# FOC_DRIVER.net
KiCad netlist of a schematic drawn in Altium Designer
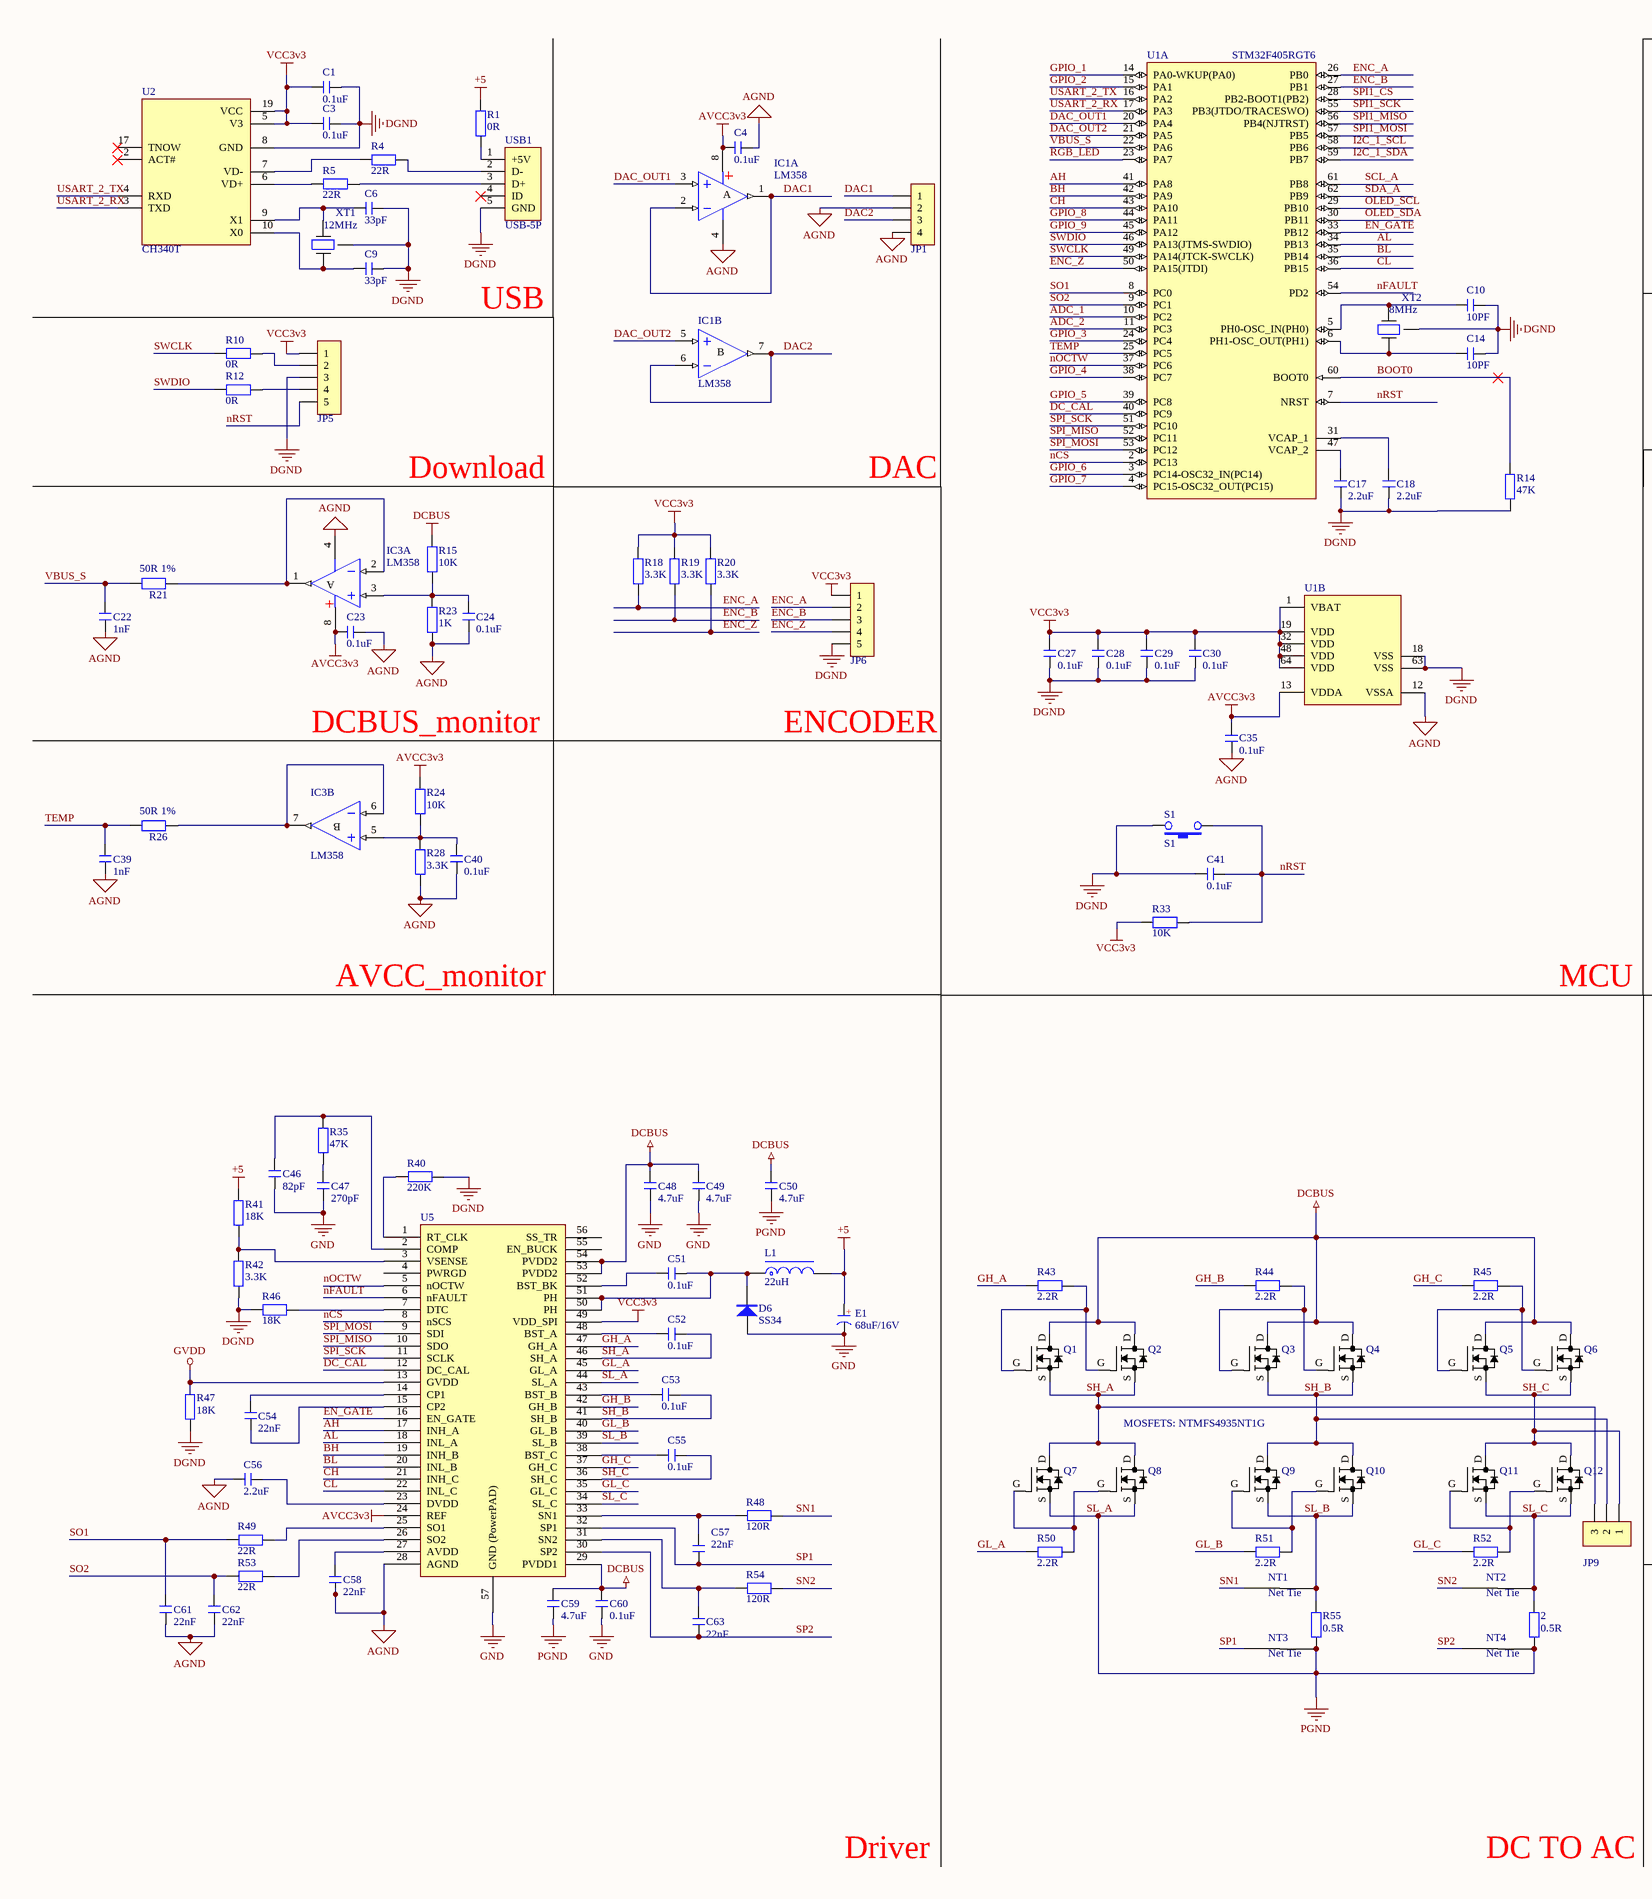
[diagram p0: FOC_DRIVER.SchDoc, left]
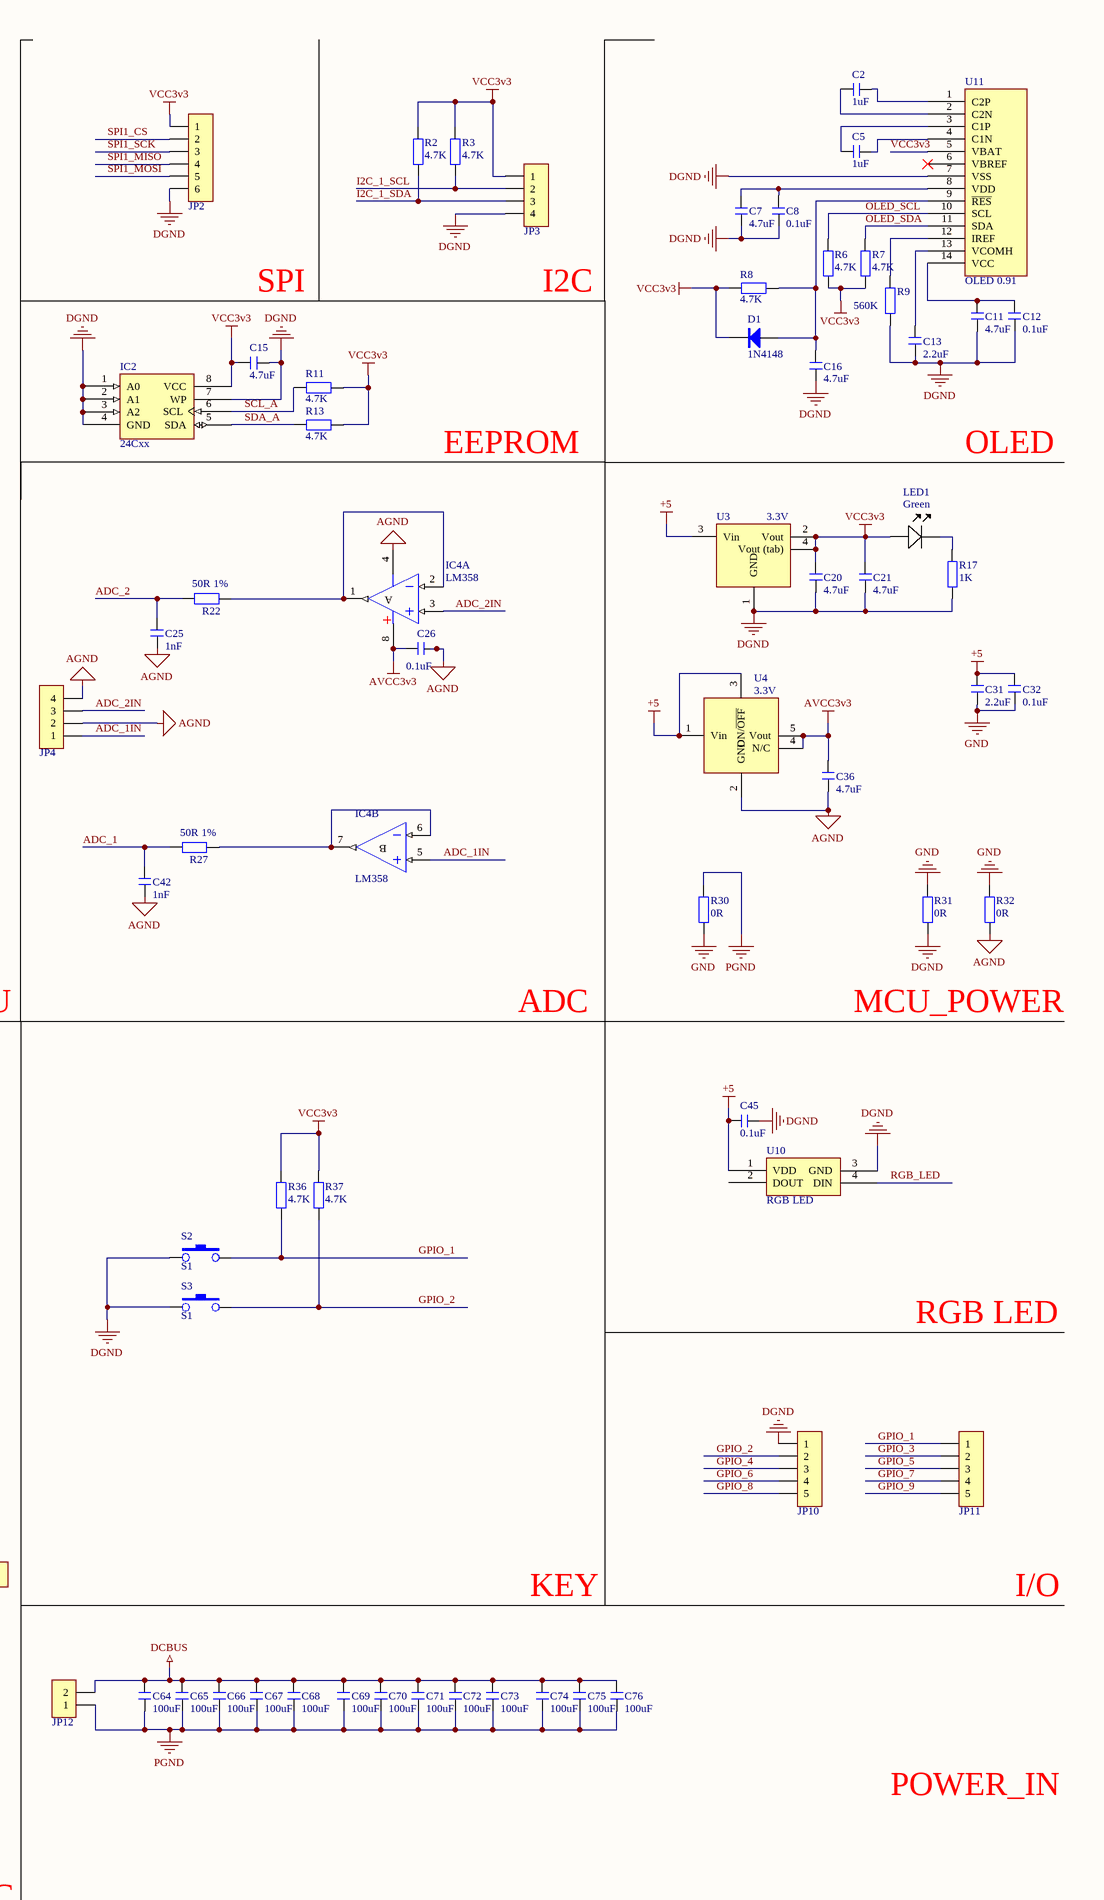
[diagram p1: FOC_DRIVER.SchDoc, right]

(export (version "E")
  (design (tool "Eeschema 10.0.6"))
  (components
    (comp (ref "2")
      (value "0.5R")
      (footprint "R 2512_L")
      (description "贴片电阻")
      (fields (field (name "版权归属") "源创客"))
      (libsource (lib "3.1   - 电阻-电容-电感") (part "R"))
    )
    (comp (ref "C1")
      (value "0.1uF")
      (footprint "C 0402_L")
      (description "无极性贴片电容")
      (fields (field (name "版权归属") "源创客"))
      (libsource (lib "3.1   - 电阻-电容-电感") (part "C"))
    )
    (comp (ref "C2")
      (value "1uF")
      (footprint "C 0402_L")
      (description "无极性贴片电容")
      (fields (field (name "版权归属") "源创客"))
      (libsource (lib "3.1   - 电阻-电容-电感") (part "C"))
    )
    (comp (ref "C3")
      (value "0.1uF")
      (footprint "C 0402_L")
      (description "无极性贴片电容")
      (fields (field (name "版权归属") "源创客"))
      (libsource (lib "3.1   - 电阻-电容-电感") (part "C"))
    )
    (comp (ref "C4")
      (value "0.1uF")
      (footprint "C 0402_L")
      (description "无极性贴片电容")
      (fields (field (name "版权归属") "源创客"))
      (libsource (lib "3.1   - 电阻-电容-电感") (part "C"))
    )
    (comp (ref "C5")
      (value "1uF")
      (footprint "C 0402_L")
      (description "无极性贴片电容")
      (fields (field (name "版权归属") "源创客"))
      (libsource (lib "3.1   - 电阻-电容-电感") (part "C"))
    )
    (comp (ref "C6")
      (value "33pF")
      (footprint "C 0402_L")
      (description "无极性贴片电容")
      (fields (field (name "版权归属") "源创客"))
      (libsource (lib "3.1   - 电阻-电容-电感") (part "C"))
    )
    (comp (ref "C7")
      (value "4.7uF")
      (footprint "C 0402_L")
      (description "无极性贴片电容")
      (fields (field (name "版权归属") "源创客"))
      (libsource (lib "3.1   - 电阻-电容-电感") (part "C"))
    )
    (comp (ref "C8")
      (value "0.1uF")
      (footprint "C 0402_L")
      (description "无极性贴片电容")
      (fields (field (name "版权归属") "源创客"))
      (libsource (lib "3.1   - 电阻-电容-电感") (part "C"))
    )
    (comp (ref "C9")
      (value "33pF")
      (footprint "C 0402_L")
      (description "无极性贴片电容")
      (fields (field (name "版权归属") "源创客"))
      (libsource (lib "3.1   - 电阻-电容-电感") (part "C"))
    )
    (comp (ref "C10")
      (value "10PF")
      (footprint "C 0402_L")
      (description "无极性贴片电容")
      (fields (field (name "版权归属") "源创客"))
      (libsource (lib "3.1   - 电阻-电容-电感") (part "C"))
    )
    (comp (ref "C11")
      (value "4.7uF")
      (footprint "C 0402_L")
      (description "无极性贴片电容")
      (fields (field (name "版权归属") "源创客"))
      (libsource (lib "3.1   - 电阻-电容-电感") (part "C"))
    )
    (comp (ref "C12")
      (value "0.1uF")
      (footprint "C 0402_L")
      (description "无极性贴片电容")
      (fields (field (name "版权归属") "源创客"))
      (libsource (lib "3.1   - 电阻-电容-电感") (part "C"))
    )
    (comp (ref "C13")
      (value "2.2uF")
      (footprint "C 0402_L")
      (description "无极性贴片电容")
      (fields (field (name "版权归属") "源创客"))
      (libsource (lib "3.1   - 电阻-电容-电感") (part "C"))
    )
    (comp (ref "C14")
      (value "10PF")
      (footprint "C 0402_L")
      (description "无极性贴片电容")
      (fields (field (name "版权归属") "源创客"))
      (libsource (lib "3.1   - 电阻-电容-电感") (part "C"))
    )
    (comp (ref "C15")
      (value "4.7uF")
      (footprint "C 0402_L")
      (description "无极性贴片电容")
      (fields (field (name "版权归属") "源创客"))
      (libsource (lib "3.1   - 电阻-电容-电感") (part "C"))
    )
    (comp (ref "C16")
      (value "4.7uF")
      (footprint "C 0402_L")
      (description "无极性贴片电容")
      (fields (field (name "版权归属") "源创客"))
      (libsource (lib "3.1   - 电阻-电容-电感") (part "C"))
    )
    (comp (ref "C17")
      (value "2.2uF")
      (footprint "C 0402_L")
      (description "无极性贴片电容")
      (fields (field (name "版权归属") "源创客"))
      (libsource (lib "3.1   - 电阻-电容-电感") (part "C"))
    )
    (comp (ref "C18")
      (value "2.2uF")
      (footprint "C 0402_L")
      (description "无极性贴片电容")
      (fields (field (name "版权归属") "源创客"))
      (libsource (lib "3.1   - 电阻-电容-电感") (part "C"))
    )
    (comp (ref "C20")
      (value "4.7uF")
      (footprint "C 0402_L")
      (description "无极性贴片电容")
      (fields (field (name "版权归属") "源创客"))
      (libsource (lib "3.1   - 电阻-电容-电感") (part "C"))
    )
    (comp (ref "C21")
      (value "4.7uF")
      (footprint "C 0402_L")
      (description "无极性贴片电容")
      (fields (field (name "版权归属") "源创客"))
      (libsource (lib "3.1   - 电阻-电容-电感") (part "C"))
    )
    (comp (ref "C22")
      (value "1nF")
      (footprint "C 0402_L")
      (description "无极性贴片电容")
      (fields (field (name "版权归属") "源创客"))
      (libsource (lib "3.1   - 电阻-电容-电感") (part "C"))
    )
    (comp (ref "C23")
      (value "0.1uF")
      (footprint "C 0402_L")
      (description "无极性贴片电容")
      (fields (field (name "版权归属") "源创客"))
      (libsource (lib "3.1   - 电阻-电容-电感") (part "C"))
    )
    (comp (ref "C24")
      (value "0.1uF")
      (footprint "C 0402_L")
      (description "无极性贴片电容")
      (fields (field (name "版权归属") "源创客"))
      (libsource (lib "3.1   - 电阻-电容-电感") (part "C"))
    )
    (comp (ref "C25")
      (value "1nF")
      (footprint "C 0402_L")
      (description "无极性贴片电容")
      (fields (field (name "版权归属") "源创客"))
      (libsource (lib "3.1   - 电阻-电容-电感") (part "C"))
    )
    (comp (ref "C26")
      (value "0.1uF")
      (footprint "C 0402_L")
      (description "无极性贴片电容")
      (fields (field (name "版权归属") "源创客"))
      (libsource (lib "3.1   - 电阻-电容-电感") (part "C"))
    )
    (comp (ref "C27")
      (value "0.1uF")
      (footprint "C 0402_L")
      (description "无极性贴片电容")
      (fields (field (name "版权归属") "源创客"))
      (libsource (lib "3.1   - 电阻-电容-电感") (part "C"))
    )
    (comp (ref "C28")
      (value "0.1uF")
      (footprint "C 0402_L")
      (description "无极性贴片电容")
      (fields (field (name "版权归属") "源创客"))
      (libsource (lib "3.1   - 电阻-电容-电感") (part "C"))
    )
    (comp (ref "C29")
      (value "0.1uF")
      (footprint "C 0402_L")
      (description "无极性贴片电容")
      (fields (field (name "版权归属") "源创客"))
      (libsource (lib "3.1   - 电阻-电容-电感") (part "C"))
    )
    (comp (ref "C30")
      (value "0.1uF")
      (footprint "C 0402_L")
      (description "无极性贴片电容")
      (fields (field (name "版权归属") "源创客"))
      (libsource (lib "3.1   - 电阻-电容-电感") (part "C"))
    )
    (comp (ref "C31")
      (value "2.2uF")
      (footprint "C 0402_L")
      (description "无极性贴片电容")
      (fields (field (name "版权归属") "源创客"))
      (libsource (lib "3.1   - 电阻-电容-电感") (part "C"))
    )
    (comp (ref "C32")
      (value "0.1uF")
      (footprint "C 0402_L")
      (description "无极性贴片电容")
      (fields (field (name "版权归属") "源创客"))
      (libsource (lib "3.1   - 电阻-电容-电感") (part "C"))
    )
    (comp (ref "C35")
      (value "0.1uF")
      (footprint "C 0402_L")
      (description "无极性贴片电容")
      (fields (field (name "版权归属") "源创客"))
      (libsource (lib "3.1   - 电阻-电容-电感") (part "C"))
    )
    (comp (ref "C36")
      (value "4.7uF")
      (footprint "C 0402_L")
      (description "无极性贴片电容")
      (fields (field (name "版权归属") "源创客"))
      (libsource (lib "3.1   - 电阻-电容-电感") (part "C"))
    )
    (comp (ref "C39")
      (value "1nF")
      (footprint "C 0402_L")
      (description "无极性贴片电容")
      (fields (field (name "版权归属") "源创客"))
      (libsource (lib "3.1   - 电阻-电容-电感") (part "C"))
    )
    (comp (ref "C40")
      (value "0.1uF")
      (footprint "C 0402_L")
      (description "无极性贴片电容")
      (fields (field (name "版权归属") "源创客"))
      (libsource (lib "3.1   - 电阻-电容-电感") (part "C"))
    )
    (comp (ref "C41")
      (value "0.1uF")
      (footprint "C 0402_L")
      (description "无极性贴片电容")
      (fields (field (name "版权归属") "源创客"))
      (libsource (lib "3.1   - 电阻-电容-电感") (part "C"))
    )
    (comp (ref "C42")
      (value "1nF")
      (footprint "C 0402_L")
      (description "无极性贴片电容")
      (fields (field (name "版权归属") "源创客"))
      (libsource (lib "3.1   - 电阻-电容-电感") (part "C"))
    )
    (comp (ref "C45")
      (value "0.1uF")
      (footprint "C 0402_L")
      (description "无极性贴片电容")
      (fields (field (name "版权归属") "源创客"))
      (libsource (lib "3.1   - 电阻-电容-电感") (part "C"))
    )
    (comp (ref "C46")
      (value "82pF")
      (footprint "C 0402_L")
      (description "无极性贴片电容")
      (fields (field (name "版权归属") "源创客"))
      (libsource (lib "3.1   - 电阻-电容-电感") (part "C"))
    )
    (comp (ref "C47")
      (value "270pF")
      (footprint "C 0402_L")
      (description "无极性贴片电容")
      (fields (field (name "版权归属") "源创客"))
      (libsource (lib "3.1   - 电阻-电容-电感") (part "C"))
    )
    (comp (ref "C48")
      (value "4.7uF")
      (footprint "C 0402_L")
      (description "无极性贴片电容")
      (fields (field (name "版权归属") "源创客"))
      (libsource (lib "3.1   - 电阻-电容-电感") (part "C"))
    )
    (comp (ref "C49")
      (value "4.7uF")
      (footprint "C 0402_L")
      (description "无极性贴片电容")
      (fields (field (name "版权归属") "源创客"))
      (libsource (lib "3.1   - 电阻-电容-电感") (part "C"))
    )
    (comp (ref "C50")
      (value "4.7uF")
      (footprint "C 0402_L")
      (description "无极性贴片电容")
      (fields (field (name "版权归属") "源创客"))
      (libsource (lib "3.1   - 电阻-电容-电感") (part "C"))
    )
    (comp (ref "C51")
      (value "0.1uF")
      (footprint "C 0402_L")
      (description "无极性贴片电容")
      (fields (field (name "版权归属") "源创客"))
      (libsource (lib "3.1   - 电阻-电容-电感") (part "C"))
    )
    (comp (ref "C52")
      (value "0.1uF")
      (footprint "C 0402_L")
      (description "无极性贴片电容")
      (fields (field (name "版权归属") "源创客"))
      (libsource (lib "3.1   - 电阻-电容-电感") (part "C"))
    )
    (comp (ref "C53")
      (value "0.1uF")
      (footprint "C 0402_L")
      (description "无极性贴片电容")
      (fields (field (name "版权归属") "源创客"))
      (libsource (lib "3.1   - 电阻-电容-电感") (part "C"))
    )
    (comp (ref "C54")
      (value "22nF")
      (footprint "C 0402_L")
      (description "无极性贴片电容")
      (fields (field (name "版权归属") "源创客"))
      (libsource (lib "3.1   - 电阻-电容-电感") (part "C"))
    )
    (comp (ref "C55")
      (value "0.1uF")
      (footprint "C 0402_L")
      (description "无极性贴片电容")
      (fields (field (name "版权归属") "源创客"))
      (libsource (lib "3.1   - 电阻-电容-电感") (part "C"))
    )
    (comp (ref "C56")
      (value "2.2uF")
      (footprint "C 0402_L")
      (description "无极性贴片电容")
      (fields (field (name "版权归属") "源创客"))
      (libsource (lib "3.1   - 电阻-电容-电感") (part "C"))
    )
    (comp (ref "C57")
      (value "22nF")
      (footprint "C 0402_L")
      (description "无极性贴片电容")
      (fields (field (name "版权归属") "源创客"))
      (libsource (lib "3.1   - 电阻-电容-电感") (part "C"))
    )
    (comp (ref "C58")
      (value "22nF")
      (footprint "C 0402_L")
      (description "无极性贴片电容")
      (fields (field (name "版权归属") "源创客"))
      (libsource (lib "3.1   - 电阻-电容-电感") (part "C"))
    )
    (comp (ref "C59")
      (value "4.7uF")
      (footprint "C 0402_L")
      (description "无极性贴片电容")
      (fields (field (name "版权归属") "源创客"))
      (libsource (lib "3.1   - 电阻-电容-电感") (part "C"))
    )
    (comp (ref "C60")
      (value "0.1uF")
      (footprint "C 0402_L")
      (description "无极性贴片电容")
      (fields (field (name "版权归属") "源创客"))
      (libsource (lib "3.1   - 电阻-电容-电感") (part "C"))
    )
    (comp (ref "C61")
      (value "22nF")
      (footprint "C 0402_L")
      (description "无极性贴片电容")
      (fields (field (name "版权归属") "源创客"))
      (libsource (lib "3.1   - 电阻-电容-电感") (part "C"))
    )
    (comp (ref "C62")
      (value "22nF")
      (footprint "C 0402_L")
      (description "无极性贴片电容")
      (fields (field (name "版权归属") "源创客"))
      (libsource (lib "3.1   - 电阻-电容-电感") (part "C"))
    )
    (comp (ref "C63")
      (value "22nF")
      (footprint "C 0402_L")
      (description "无极性贴片电容")
      (fields (field (name "版权归属") "源创客"))
      (libsource (lib "3.1   - 电阻-电容-电感") (part "C"))
    )
    (comp (ref "C64")
      (value "100uF")
      (footprint "C 1210_L")
      (description "无极性贴片电容")
      (fields (field (name "版权归属") "源创客"))
      (libsource (lib "3.1   - 电阻-电容-电感") (part "C"))
    )
    (comp (ref "C65")
      (value "100uF")
      (footprint "C 1210_L")
      (description "无极性贴片电容")
      (fields (field (name "版权归属") "源创客"))
      (libsource (lib "3.1   - 电阻-电容-电感") (part "C"))
    )
    (comp (ref "C66")
      (value "100uF")
      (footprint "C 1210_L")
      (description "无极性贴片电容")
      (fields (field (name "版权归属") "源创客"))
      (libsource (lib "3.1   - 电阻-电容-电感") (part "C"))
    )
    (comp (ref "C67")
      (value "100uF")
      (footprint "C 1210_L")
      (description "无极性贴片电容")
      (fields (field (name "版权归属") "源创客"))
      (libsource (lib "3.1   - 电阻-电容-电感") (part "C"))
    )
    (comp (ref "C68")
      (value "100uF")
      (footprint "C 1210_L")
      (description "无极性贴片电容")
      (fields (field (name "版权归属") "源创客"))
      (libsource (lib "3.1   - 电阻-电容-电感") (part "C"))
    )
    (comp (ref "C69")
      (value "100uF")
      (footprint "C 1210_L")
      (description "无极性贴片电容")
      (fields (field (name "版权归属") "源创客"))
      (libsource (lib "3.1   - 电阻-电容-电感") (part "C"))
    )
    (comp (ref "C70")
      (value "100uF")
      (footprint "C 1210_L")
      (description "无极性贴片电容")
      (fields (field (name "版权归属") "源创客"))
      (libsource (lib "3.1   - 电阻-电容-电感") (part "C"))
    )
    (comp (ref "C71")
      (value "100uF")
      (footprint "C 1210_L")
      (description "无极性贴片电容")
      (fields (field (name "版权归属") "源创客"))
      (libsource (lib "3.1   - 电阻-电容-电感") (part "C"))
    )
    (comp (ref "C72")
      (value "100uF")
      (footprint "C 1210_L")
      (description "无极性贴片电容")
      (fields (field (name "版权归属") "源创客"))
      (libsource (lib "3.1   - 电阻-电容-电感") (part "C"))
    )
    (comp (ref "C73")
      (value "100uF")
      (footprint "C 1210_L")
      (description "无极性贴片电容")
      (fields (field (name "版权归属") "源创客"))
      (libsource (lib "3.1   - 电阻-电容-电感") (part "C"))
    )
    (comp (ref "C74")
      (value "100uF")
      (footprint "C 1210_L")
      (description "无极性贴片电容")
      (fields (field (name "版权归属") "源创客"))
      (libsource (lib "3.1   - 电阻-电容-电感") (part "C"))
    )
    (comp (ref "C75")
      (value "100uF")
      (footprint "C 1210_L")
      (description "无极性贴片电容")
      (fields (field (name "版权归属") "源创客"))
      (libsource (lib "3.1   - 电阻-电容-电感") (part "C"))
    )
    (comp (ref "C76")
      (value "100uF")
      (footprint "C 1210_L")
      (description "无极性贴片电容")
      (fields (field (name "版权归属") "源创客"))
      (libsource (lib "3.1   - 电阻-电容-电感") (part "C"))
    )
    (comp (ref "D1")
      (value "1N4148")
      (footprint "SOD-323")
      (description "高速开关二极管")
      (fields (field (name "版权归属") "源创客"))
      (libsource (lib "8.1   - 二极管-整流桥") (part "1N4148"))
    )
    (comp (ref "D6")
      (value "SS34")
      (footprint "DO214_SMA")
      (description "肖特基二极管")
      (fields (field (name "版权归属") "源创客"))
      (libsource (lib "8.1   - 二极管-整流桥") (part "SS34"))
    )
    (comp (ref "E1")
      (value "68uF/16V")
      (footprint "CD C(6032)")
      (description "贴片钽电容")
      (fields (field (name "版权归属") "源创客"))
      (libsource (lib "3.1   - 电阻-电容-电感") (part "C-CD"))
    )
    (comp (ref "IC1")
      (value "LM358")
      (footprint "SOP8_N")
      (description "双路运放")
      (fields (field (name "版权归属") "源创客"))
      (libsource (lib "1.1   - IC芯片") (part "LM358"))
    )
    (comp (ref "IC2")
      (value "24Cxx")
      (footprint "SOP8_L")
      (description "外置EEPROM")
      (fields (field (name "版权归属") "源创客"))
      (libsource (lib "1.1   - IC芯片") (part "24Cxx"))
    )
    (comp (ref "IC3")
      (value "LM358")
      (footprint "SOP8_N")
      (description "双路运放")
      (fields (field (name "版权归属") "源创客"))
      (libsource (lib "1.1   - IC芯片") (part "LM358"))
    )
    (comp (ref "IC4")
      (value "LM358")
      (footprint "SOP8_N")
      (description "双路运放")
      (fields (field (name "版权归属") "源创客"))
      (libsource (lib "1.1   - IC芯片") (part "LM358"))
    )
    (comp (ref "JP1")
      (value "HDR-1X4")
      (footprint "MX 1.25-WS-4P")
      (description "4P接插件")
      (fields (field (name "版权归属") "源创客"))
      (libsource (lib "") (part "Header 4_1"))
    )
    (comp (ref "JP2")
      (value "HDR-1X6")
      (footprint "MX 1.25-WS-6P")
      (description "6P接插件")
      (fields (field (name "版权归属") "源创客"))
      (libsource (lib "4.2   - 接插件-脚距1.25") (part "Header 6"))
    )
    (comp (ref "JP3")
      (value "HDR-1X4")
      (footprint "MX 1.25-WS-4P")
      (description "4P接插件")
      (fields (field (name "版权归属") "源创客"))
      (libsource (lib "") (part "Header 4_1"))
    )
    (comp (ref "JP4")
      (value "HDR-1X4")
      (footprint "MX 1.25-WS-4P")
      (description "4P接插件")
      (fields (field (name "版权归属") "源创客"))
      (libsource (lib "4.2   - 接插件-脚距1.25") (part "Header 4"))
    )
    (comp (ref "JP5")
      (value "HDR-1X5")
      (footprint "HDR2.54-WS-5P")
      (description "5P接插件")
      (fields (field (name "版权归属") "源创客"))
      (libsource (lib "4.5   - 接插件-脚距2.54") (part "Header 5"))
    )
    (comp (ref "JP6")
      (value "HDR-1X5")
      (footprint "HDR2.54-WS-5P")
      (description "5P接插件")
      (fields (field (name "版权归属") "源创客"))
      (libsource (lib "4.5   - 接插件-脚距2.54") (part "Header 5"))
    )
    (comp (ref "JP9")
      (value "HDR-1X3")
      (footprint "KF128-5.08-3P")
      (description "3P接插件")
      (fields (field (name "版权归属") "源创客"))
      (libsource (lib "4.10 - 接插件-脚距5.08") (part "Header 3"))
    )
    (comp (ref "JP10")
      (value "HDR-1X5")
      (footprint "HDR2.54-WS-5P")
      (description "5P接插件")
      (fields (field (name "版权归属") "源创客"))
      (libsource (lib "4.5   - 接插件-脚距2.54") (part "Header 5"))
    )
    (comp (ref "JP11")
      (value "HDR-1X5")
      (footprint "HDR2.54-WS-5P")
      (description "5P接插件")
      (fields (field (name "版权归属") "源创客"))
      (libsource (lib "4.5   - 接插件-脚距2.54") (part "Header 5"))
    )
    (comp (ref "JP12")
      (value "HDR-1X2")
      (footprint "KF128-5.08-2P")
      (description "2P接插件")
      (fields (field (name "版权归属") "源创客"))
      (libsource (lib "4.10 - 接插件-脚距5.08") (part "Header 2"))
    )
    (comp (ref "L1")
      (value "22uH")
      (footprint "CD42")
      (description "贴片功率电感")
      (fields (field (name "版权归属") "源创客"))
      (libsource (lib "3.1   - 电阻-电容-电感") (part "L-CD"))
    )
    (comp (ref "LED1")
      (value "Green")
      (footprint "LED-0603-GREEN")
      (description "LED GREEN CLEAR 0603 SMD")
      (fields
        (field (name "MANUFACTURER") "Lite-On Inc.")
        (field (name "MANUFACTURER PART NUMBER") "LTST-C190KGKT")
      )
      (libsource (lib "CustomComponents") (part "LTST-C190KGKT"))
    )
    (comp (ref "NT1")
      (value "0.25mm")
      (footprint "NetTie_0.25mm")
      (libsource (lib "CustomComponents") (part "NetTie_0.25mm"))
    )
    (comp (ref "NT2")
      (value "0.25mm")
      (footprint "NetTie_0.25mm")
      (libsource (lib "CustomComponents") (part "NetTie_0.25mm"))
    )
    (comp (ref "NT3")
      (value "0.25mm")
      (footprint "NetTie_0.25mm")
      (libsource (lib "CustomComponents") (part "NetTie_0.25mm"))
    )
    (comp (ref "NT4")
      (value "0.25mm")
      (footprint "NetTie_0.25mm")
      (libsource (lib "CustomComponents") (part "NetTie_0.25mm"))
    )
    (comp (ref "Q1")
      (value "~")
      (footprint "SO8FL")
      (description "MOSFET N-CH 30V 13A SO8FL")
      (fields
        (field (name "MANUFACTURER") "ON Semiconductor")
        (field (name "MANUFACTURER PART NUMBER") "NTMFS4935NT1G")
      )
      (libsource (lib "CustomComponents") (part "NTMFS4935NT1G"))
    )
    (comp (ref "Q2")
      (value "FILL_FOOTPRINT")
      (footprint "SO8FL")
      (description "MOSFET N-CH 30V 13A SO8FL")
      (fields
        (field (name "MANUFACTURER") "ON Semiconductor")
        (field (name "MANUFACTURER PART NUMBER") "NTMFS4935NT1G")
      )
      (libsource (lib "CustomComponents") (part "NTMFS4935NT1G"))
    )
    (comp (ref "Q3")
      (value "~")
      (footprint "SO8FL")
      (description "MOSFET N-CH 30V 13A SO8FL")
      (fields
        (field (name "MANUFACTURER") "ON Semiconductor")
        (field (name "MANUFACTURER PART NUMBER") "NTMFS4935NT1G")
      )
      (libsource (lib "CustomComponents") (part "NTMFS4935NT1G"))
    )
    (comp (ref "Q4")
      (value "FILL_FOOTPRINT")
      (footprint "SO8FL")
      (description "MOSFET N-CH 30V 13A SO8FL")
      (fields
        (field (name "MANUFACTURER") "ON Semiconductor")
        (field (name "MANUFACTURER PART NUMBER") "NTMFS4935NT1G")
      )
      (libsource (lib "CustomComponents") (part "NTMFS4935NT1G"))
    )
    (comp (ref "Q5")
      (value "~")
      (footprint "SO8FL")
      (description "MOSFET N-CH 30V 13A SO8FL")
      (fields
        (field (name "MANUFACTURER") "ON Semiconductor")
        (field (name "MANUFACTURER PART NUMBER") "NTMFS4935NT1G")
      )
      (libsource (lib "CustomComponents") (part "NTMFS4935NT1G"))
    )
    (comp (ref "Q6")
      (value "FILL_FOOTPRINT")
      (footprint "SO8FL")
      (description "MOSFET N-CH 30V 13A SO8FL")
      (fields
        (field (name "MANUFACTURER") "ON Semiconductor")
        (field (name "MANUFACTURER PART NUMBER") "NTMFS4935NT1G")
      )
      (libsource (lib "CustomComponents") (part "NTMFS4935NT1G"))
    )
    (comp (ref "Q7")
      (value "~")
      (footprint "SO8FL")
      (description "MOSFET N-CH 30V 13A SO8FL")
      (fields
        (field (name "MANUFACTURER") "ON Semiconductor")
        (field (name "MANUFACTURER PART NUMBER") "NTMFS4935NT1G")
      )
      (libsource (lib "CustomComponents") (part "NTMFS4935NT1G"))
    )
    (comp (ref "Q8")
      (value "~")
      (footprint "SO8FL")
      (description "MOSFET N-CH 30V 13A SO8FL")
      (fields
        (field (name "MANUFACTURER") "ON Semiconductor")
        (field (name "MANUFACTURER PART NUMBER") "NTMFS4935NT1G")
      )
      (libsource (lib "CustomComponents") (part "NTMFS4935NT1G"))
    )
    (comp (ref "Q9")
      (value "~")
      (footprint "SO8FL")
      (description "MOSFET N-CH 30V 13A SO8FL")
      (fields
        (field (name "MANUFACTURER") "ON Semiconductor")
        (field (name "MANUFACTURER PART NUMBER") "NTMFS4935NT1G")
      )
      (libsource (lib "CustomComponents") (part "NTMFS4935NT1G"))
    )
    (comp (ref "Q10")
      (value "~")
      (footprint "SO8FL")
      (description "MOSFET N-CH 30V 13A SO8FL")
      (fields
        (field (name "MANUFACTURER") "ON Semiconductor")
        (field (name "MANUFACTURER PART NUMBER") "NTMFS4935NT1G")
      )
      (libsource (lib "CustomComponents") (part "NTMFS4935NT1G"))
    )
    (comp (ref "Q11")
      (value "~")
      (footprint "SO8FL")
      (description "MOSFET N-CH 30V 13A SO8FL")
      (fields
        (field (name "MANUFACTURER") "ON Semiconductor")
        (field (name "MANUFACTURER PART NUMBER") "NTMFS4935NT1G")
      )
      (libsource (lib "CustomComponents") (part "NTMFS4935NT1G"))
    )
    (comp (ref "Q12")
      (value "~")
      (footprint "SO8FL")
      (description "MOSFET N-CH 30V 13A SO8FL")
      (fields
        (field (name "MANUFACTURER") "ON Semiconductor")
        (field (name "MANUFACTURER PART NUMBER") "NTMFS4935NT1G")
      )
      (libsource (lib "CustomComponents") (part "NTMFS4935NT1G"))
    )
    (comp (ref "R1")
      (value "0R")
      (footprint "R 0402_L")
      (description "贴片电阻")
      (fields (field (name "版权归属") "源创客"))
      (libsource (lib "3.1   - 电阻-电容-电感") (part "R"))
    )
    (comp (ref "R2")
      (value "4.7K")
      (footprint "R 0402_L")
      (description "贴片电阻")
      (fields (field (name "版权归属") "源创客"))
      (libsource (lib "3.1   - 电阻-电容-电感") (part "R"))
    )
    (comp (ref "R3")
      (value "4.7K")
      (footprint "R 0402_L")
      (description "贴片电阻")
      (fields (field (name "版权归属") "源创客"))
      (libsource (lib "3.1   - 电阻-电容-电感") (part "R"))
    )
    (comp (ref "R4")
      (value "22R")
      (footprint "R 0402_L")
      (description "贴片电阻")
      (fields (field (name "版权归属") "源创客"))
      (libsource (lib "3.1   - 电阻-电容-电感") (part "R"))
    )
    (comp (ref "R5")
      (value "22R")
      (footprint "R 0402_L")
      (description "贴片电阻")
      (fields (field (name "版权归属") "源创客"))
      (libsource (lib "3.1   - 电阻-电容-电感") (part "R"))
    )
    (comp (ref "R6")
      (value "4.7K")
      (footprint "R 0402_L")
      (description "贴片电阻")
      (fields (field (name "版权归属") "源创客"))
      (libsource (lib "3.1   - 电阻-电容-电感") (part "R"))
    )
    (comp (ref "R7")
      (value "4.7K")
      (footprint "R 0402_L")
      (description "贴片电阻")
      (fields (field (name "版权归属") "源创客"))
      (libsource (lib "3.1   - 电阻-电容-电感") (part "R"))
    )
    (comp (ref "R8")
      (value "4.7K")
      (footprint "R 0402_L")
      (description "贴片电阻")
      (fields (field (name "版权归属") "源创客"))
      (libsource (lib "3.1   - 电阻-电容-电感") (part "R"))
    )
    (comp (ref "R9")
      (value "560K")
      (footprint "R 0402_L")
      (description "贴片电阻")
      (fields (field (name "版权归属") "源创客"))
      (libsource (lib "3.1   - 电阻-电容-电感") (part "R"))
    )
    (comp (ref "R10")
      (value "0R")
      (footprint "R 0402_L")
      (description "贴片电阻")
      (fields (field (name "版权归属") "源创客"))
      (libsource (lib "3.1   - 电阻-电容-电感") (part "R"))
    )
    (comp (ref "R11")
      (value "4.7K")
      (footprint "R 0402_L")
      (description "贴片电阻")
      (fields (field (name "版权归属") "源创客"))
      (libsource (lib "3.1   - 电阻-电容-电感") (part "R"))
    )
    (comp (ref "R12")
      (value "0R")
      (footprint "R 0402_L")
      (description "贴片电阻")
      (fields (field (name "版权归属") "源创客"))
      (libsource (lib "3.1   - 电阻-电容-电感") (part "R"))
    )
    (comp (ref "R13")
      (value "4.7K")
      (footprint "R 0402_L")
      (description "贴片电阻")
      (fields (field (name "版权归属") "源创客"))
      (libsource (lib "3.1   - 电阻-电容-电感") (part "R"))
    )
    (comp (ref "R14")
      (value "47K")
      (footprint "R 0402_L")
      (description "贴片电阻")
      (fields (field (name "版权归属") "源创客"))
      (libsource (lib "3.1   - 电阻-电容-电感") (part "R"))
    )
    (comp (ref "R15")
      (value "10K")
      (footprint "R 0402_L")
      (description "贴片电阻")
      (fields (field (name "版权归属") "源创客"))
      (libsource (lib "3.1   - 电阻-电容-电感") (part "R"))
    )
    (comp (ref "R17")
      (value "1K")
      (footprint "R 0402_L")
      (description "贴片电阻")
      (fields (field (name "版权归属") "源创客"))
      (libsource (lib "3.1   - 电阻-电容-电感") (part "R"))
    )
    (comp (ref "R18")
      (value "3.3K")
      (footprint "R 0402_L")
      (description "贴片电阻")
      (fields (field (name "版权归属") "源创客"))
      (libsource (lib "3.1   - 电阻-电容-电感") (part "R"))
    )
    (comp (ref "R19")
      (value "3.3K")
      (footprint "R 0402_L")
      (description "贴片电阻")
      (fields (field (name "版权归属") "源创客"))
      (libsource (lib "3.1   - 电阻-电容-电感") (part "R"))
    )
    (comp (ref "R20")
      (value "3.3K")
      (footprint "R 0402_L")
      (description "贴片电阻")
      (fields (field (name "版权归属") "源创客"))
      (libsource (lib "3.1   - 电阻-电容-电感") (part "R"))
    )
    (comp (ref "R21")
      (value "50R 1%")
      (footprint "R 0402_L")
      (description "贴片电阻")
      (fields (field (name "版权归属") "源创客"))
      (libsource (lib "3.1   - 电阻-电容-电感") (part "R"))
    )
    (comp (ref "R22")
      (value "50R 1%")
      (footprint "R 0402_L")
      (description "贴片电阻")
      (fields (field (name "版权归属") "源创客"))
      (libsource (lib "3.1   - 电阻-电容-电感") (part "R"))
    )
    (comp (ref "R23")
      (value "1K")
      (footprint "R 0402_L")
      (description "贴片电阻")
      (fields (field (name "版权归属") "源创客"))
      (libsource (lib "3.1   - 电阻-电容-电感") (part "R"))
    )
    (comp (ref "R24")
      (value "10K")
      (footprint "R 0402_L")
      (description "贴片电阻")
      (fields (field (name "版权归属") "源创客"))
      (libsource (lib "3.1   - 电阻-电容-电感") (part "R"))
    )
    (comp (ref "R26")
      (value "50R 1%")
      (footprint "R 0402_L")
      (description "贴片电阻")
      (fields (field (name "版权归属") "源创客"))
      (libsource (lib "3.1   - 电阻-电容-电感") (part "R"))
    )
    (comp (ref "R27")
      (value "50R 1%")
      (footprint "R 0402_L")
      (description "贴片电阻")
      (fields (field (name "版权归属") "源创客"))
      (libsource (lib "3.1   - 电阻-电容-电感") (part "R"))
    )
    (comp (ref "R28")
      (value "3.3K")
      (footprint "R 0402_L")
      (description "贴片电阻")
      (fields (field (name "版权归属") "源创客"))
      (libsource (lib "3.1   - 电阻-电容-电感") (part "R"))
    )
    (comp (ref "R30")
      (value "0R")
      (footprint "R 0603_L")
      (description "贴片电阻")
      (fields (field (name "版权归属") "源创客"))
      (libsource (lib "3.1   - 电阻-电容-电感") (part "R"))
    )
    (comp (ref "R31")
      (value "0R")
      (footprint "R 0603_L")
      (description "贴片电阻")
      (fields (field (name "版权归属") "源创客"))
      (libsource (lib "3.1   - 电阻-电容-电感") (part "R"))
    )
    (comp (ref "R32")
      (value "0R")
      (footprint "R 0603_L")
      (description "贴片电阻")
      (fields (field (name "版权归属") "源创客"))
      (libsource (lib "3.1   - 电阻-电容-电感") (part "R"))
    )
    (comp (ref "R33")
      (value "10K")
      (footprint "R 0402_L")
      (description "贴片电阻")
      (fields (field (name "版权归属") "源创客"))
      (libsource (lib "3.1   - 电阻-电容-电感") (part "R"))
    )
    (comp (ref "R35")
      (value "47K")
      (footprint "R 0402_L")
      (description "贴片电阻")
      (fields (field (name "版权归属") "源创客"))
      (libsource (lib "3.1   - 电阻-电容-电感") (part "R"))
    )
    (comp (ref "R36")
      (value "4.7K")
      (footprint "R 0402_L")
      (description "贴片电阻")
      (fields (field (name "版权归属") "源创客"))
      (libsource (lib "3.1   - 电阻-电容-电感") (part "R"))
    )
    (comp (ref "R37")
      (value "4.7K")
      (footprint "R 0402_L")
      (description "贴片电阻")
      (fields (field (name "版权归属") "源创客"))
      (libsource (lib "3.1   - 电阻-电容-电感") (part "R"))
    )
    (comp (ref "R40")
      (value "220K")
      (footprint "R 0402_L")
      (description "贴片电阻")
      (fields (field (name "版权归属") "源创客"))
      (libsource (lib "3.1   - 电阻-电容-电感") (part "R"))
    )
    (comp (ref "R41")
      (value "18K")
      (footprint "R 0402_L")
      (description "贴片电阻")
      (fields (field (name "版权归属") "源创客"))
      (libsource (lib "3.1   - 电阻-电容-电感") (part "R"))
    )
    (comp (ref "R42")
      (value "3.3K")
      (footprint "R 0402_L")
      (description "贴片电阻")
      (fields (field (name "版权归属") "源创客"))
      (libsource (lib "3.1   - 电阻-电容-电感") (part "R"))
    )
    (comp (ref "R43")
      (value "2.2R")
      (footprint "R 0402_L")
      (description "贴片电阻")
      (fields (field (name "版权归属") "源创客"))
      (libsource (lib "3.1   - 电阻-电容-电感") (part "R"))
    )
    (comp (ref "R44")
      (value "2.2R")
      (footprint "R 0402_L")
      (description "贴片电阻")
      (fields (field (name "版权归属") "源创客"))
      (libsource (lib "3.1   - 电阻-电容-电感") (part "R"))
    )
    (comp (ref "R45")
      (value "2.2R")
      (footprint "R 0402_L")
      (description "贴片电阻")
      (fields (field (name "版权归属") "源创客"))
      (libsource (lib "3.1   - 电阻-电容-电感") (part "R"))
    )
    (comp (ref "R46")
      (value "18K")
      (footprint "R 0402_L")
      (description "贴片电阻")
      (fields (field (name "版权归属") "源创客"))
      (libsource (lib "3.1   - 电阻-电容-电感") (part "R"))
    )
    (comp (ref "R47")
      (value "18K")
      (footprint "R 0402_L")
      (description "贴片电阻")
      (fields (field (name "版权归属") "源创客"))
      (libsource (lib "3.1   - 电阻-电容-电感") (part "R"))
    )
    (comp (ref "R48")
      (value "120R")
      (footprint "R 0402_L")
      (description "贴片电阻")
      (fields (field (name "版权归属") "源创客"))
      (libsource (lib "3.1   - 电阻-电容-电感") (part "R"))
    )
    (comp (ref "R49")
      (value "22R")
      (footprint "R 0402_L")
      (description "贴片电阻")
      (fields (field (name "版权归属") "源创客"))
      (libsource (lib "3.1   - 电阻-电容-电感") (part "R"))
    )
    (comp (ref "R50")
      (value "2.2R")
      (footprint "R 0402_L")
      (description "贴片电阻")
      (fields (field (name "版权归属") "源创客"))
      (libsource (lib "3.1   - 电阻-电容-电感") (part "R"))
    )
    (comp (ref "R51")
      (value "2.2R")
      (footprint "R 0402_L")
      (description "贴片电阻")
      (fields (field (name "版权归属") "源创客"))
      (libsource (lib "3.1   - 电阻-电容-电感") (part "R"))
    )
    (comp (ref "R52")
      (value "2.2R")
      (footprint "R 0402_L")
      (description "贴片电阻")
      (fields (field (name "版权归属") "源创客"))
      (libsource (lib "3.1   - 电阻-电容-电感") (part "R"))
    )
    (comp (ref "R53")
      (value "22R")
      (footprint "R 0402_L")
      (description "贴片电阻")
      (fields (field (name "版权归属") "源创客"))
      (libsource (lib "3.1   - 电阻-电容-电感") (part "R"))
    )
    (comp (ref "R54")
      (value "120R")
      (footprint "R 0402_L")
      (description "贴片电阻")
      (fields (field (name "版权归属") "源创客"))
      (libsource (lib "3.1   - 电阻-电容-电感") (part "R"))
    )
    (comp (ref "R55")
      (value "0.5R")
      (footprint "R 2512_L")
      (description "贴片电阻")
      (fields (field (name "版权归属") "源创客"))
      (libsource (lib "3.1   - 电阻-电容-电感") (part "R"))
    )
    (comp (ref "S1")
      (value "S1")
      (footprint "SW-SMD_TS-1066B-B3D2")
      (description "轻触按键2P")
      (libsource (lib "Component") (part "KEY_2P"))
    )
    (comp (ref "S2")
      (value "S1")
      (footprint "SW-SMD_TS-1066B-B3D2")
      (description "轻触按键2P")
      (libsource (lib "Component") (part "KEY_2P"))
    )
    (comp (ref "S3")
      (value "S1")
      (footprint "SW-SMD_TS-1066B-B3D2")
      (description "轻触按键2P")
      (libsource (lib "Component") (part "KEY_2P"))
    )
    (comp (ref "U1")
      (value "~")
      (footprint "STM-LQFP64_N")
      (fields (field (name "MANUFACTURER") "STMicroelectronics") (field (name "PARTNUMBER") "STM32F405RGT6"))
      (libsource (lib "STMicroelectronics STM32 F4") (part "STM32F405RGT6"))
    )
    (comp (ref "U2") (value "CH340T") (footprint "CH340T") (libsource (lib "F280049") (part "CH340T")))
    (comp (ref "U3")
      (value "3.3V")
      (footprint "SOT223")
      (description "IC REG LDO 3.3V 1A SOT223")
      (fields (field (name "MANUFACTURER") "Diodes Incorporated"))
      (libsource (lib "CustomComponents") (part "AZ1117EH-3.3TRG1"))
    )
    (comp (ref "U4")
      (value "3.3V")
      (footprint "SOT23-5")
      (description "IC REG LDO 3.3V 0.25A SOT23-5")
      (fields (field (name "MANUFACTURER") "Texas Instruments"))
      (libsource (lib "CustomComponents") (part "LP5907MFX-3.3/NOPB"))
    )
    (comp (ref "U5")
      (value "~")
      (footprint "TSSOP50P810X120_HS-57N")
      (description "MOTOR DRIVER, 3PH, 56HTSSOP")
      (libsource (lib "CustomComponents") (part "DRV8301"))
    )
    (comp (ref "U10")
      (value "RGB LED")
      (footprint "LED 3528-4Pin")
      (libsource (lib "Schlib2") (part "RGB LED"))
    )
    (comp (ref "U11")
      (value "OLED 0.91")
      (footprint "OLED-SMD_QG-2832XXX")
      (libsource (lib "Schlib1") (part "OLED 0.91"))
    )
    (comp (ref "USB1")
      (value "USB-5P")
      (footprint "USB-MINI-A")
      (description "微型USB母座")
      (fields (field (name "版权归属") "源创客"))
      (libsource (lib "4.1   - 接口类") (part "USB-5P"))
    )
    (comp (ref "XT1")
      (value "12MHz")
      (footprint "OSC 3225-4P")
      (description "Crystal 8MHz ±10ppm 10pF 200 Ohm -10°C ~ 60°C Surface Mount 4-SMD, No Lead (DFN, LCC)")
      (fields
        (field (name "MANUFACTURER") "Abracon LLC")
        (field (name "MANUFACTURER PART NUMBER") "ABM3B-8.000MHZ-10-1-U-T")
      )
      (libsource (lib "CustomComponents") (part "ABM3B-8.000MHZ-10-1-U-T"))
    )
    (comp (ref "XT2")
      (value "8MHz")
      (footprint "OSC 3225-4P")
      (description "Crystal 8MHz ±10ppm 10pF 200 Ohm -10°C ~ 60°C Surface Mount 4-SMD, No Lead (DFN, LCC)")
      (fields
        (field (name "MANUFACTURER") "Abracon LLC")
        (field (name "MANUFACTURER PART NUMBER") "ABM3B-8.000MHZ-10-1-U-T")
      )
      (libsource (lib "CustomComponents") (part "ABM3B-8.000MHZ-10-1-U-T"))
    )
  )
  (nets
    (net (code "1") (name "+5") (class "Default")
      (node (ref "C31") (pin "1") (pinfunction "1_1") (pintype "passive"))
      (node (ref "C32") (pin "1") (pinfunction "1_1") (pintype "passive"))
      (node (ref "C45") (pin "1") (pinfunction "1_1") (pintype "passive"))
      (node (ref "E1") (pin "1") (pinfunction "A_1") (pintype "passive"))
      (node (ref "L1") (pin "2") (pinfunction "2_2") (pintype "passive"))
      (node (ref "R1") (pin "2") (pinfunction "2_2") (pintype "passive"))
      (node (ref "R41") (pin "1") (pinfunction "1_1") (pintype "passive"))
      (node (ref "U10") (pin "1") (pinfunction "VDD_1") (pintype "passive"))
      (node (ref "U3") (pin "3") (pinfunction "Vin_3") (pintype "passive"))
      (node (ref "U4") (pin "1") (pinfunction "Vin_1") (pintype "passive"))
      (node (ref "U4") (pin "3") (pinfunction "ON/~{OFF}_3") (pintype "passive"))
    )
    (net (code "2") (name "/ADC_1") (class "Default")
      (node (ref "C42") (pin "1") (pinfunction "1_1") (pintype "passive"))
      (node (ref "R27") (pin "2") (pinfunction "2_2") (pintype "passive"))
      (node (ref "U1") (pin "10") (pinfunction "PC2_10") (pintype "bidirectional"))
    )
    (net (code "3") (name "/ADC_1IN") (class "Default")
      (node (ref "IC4") (pin "5") (pinfunction "IN+_5") (pintype "input"))
      (node (ref "JP4") (pin "1") (pinfunction "1_1") (pintype "passive"))
    )
    (net (code "4") (name "/ADC_2") (class "Default")
      (node (ref "C25") (pin "1") (pinfunction "1_1") (pintype "passive"))
      (node (ref "R22") (pin "2") (pinfunction "2_2") (pintype "passive"))
      (node (ref "U1") (pin "11") (pinfunction "PC3_11") (pintype "bidirectional"))
    )
    (net (code "5") (name "/ADC_2IN") (class "Default")
      (node (ref "IC4") (pin "3") (pinfunction "IN+_3") (pintype "input"))
      (node (ref "JP4") (pin "3") (pinfunction "3_3") (pintype "passive"))
    )
    (net (code "6") (name "/AH") (class "Default")
      (node (ref "U1") (pin "41") (pinfunction "PA8_41") (pintype "bidirectional"))
      (node (ref "U5") (pin "17") (pinfunction "INH_A_17") (pintype "passive"))
    )
    (net (code "7") (name "/AL") (class "Default")
      (node (ref "U1") (pin "34") (pinfunction "PB13_34") (pintype "bidirectional"))
      (node (ref "U5") (pin "18") (pinfunction "INL_A_18") (pintype "passive"))
    )
    (net (code "8") (name "/BH") (class "Default")
      (node (ref "U1") (pin "42") (pinfunction "PA9_42") (pintype "bidirectional"))
      (node (ref "U5") (pin "19") (pinfunction "INH_B_19") (pintype "passive"))
    )
    (net (code "9") (name "/BL") (class "Default")
      (node (ref "U1") (pin "35") (pinfunction "PB14_35") (pintype "bidirectional"))
      (node (ref "U5") (pin "20") (pinfunction "INL_B_20") (pintype "passive"))
    )
    (net (code "10") (name "/BOOT0") (class "Default")
      (node (ref "R14") (pin "2") (pinfunction "2_2") (pintype "passive"))
      (node (ref "U1") (pin "60") (pinfunction "BOOT0_60") (pintype "input"))
    )
    (net (code "11") (name "/CH") (class "Default")
      (node (ref "U1") (pin "43") (pinfunction "PA10_43") (pintype "bidirectional"))
      (node (ref "U5") (pin "21") (pinfunction "INH_C_21") (pintype "passive"))
    )
    (net (code "12") (name "/CL") (class "Default")
      (node (ref "U1") (pin "36") (pinfunction "PB15_36") (pintype "bidirectional"))
      (node (ref "U5") (pin "22") (pinfunction "INL_C_22") (pintype "passive"))
    )
    (net (code "13") (name "/DAC1") (class "Default")
      (node (ref "IC1") (pin "1") (pinfunction "OUT_1") (pintype "output"))
      (node (ref "IC1") (pin "2") (pinfunction "IN-_2") (pintype "input"))
      (node (ref "JP1") (pin "1") (pinfunction "1_1") (pintype "passive"))
    )
    (net (code "14") (name "/DAC2") (class "Default")
      (node (ref "IC1") (pin "6") (pinfunction "IN-_6") (pintype "input"))
      (node (ref "IC1") (pin "7") (pinfunction "OUT_7") (pintype "output"))
      (node (ref "JP1") (pin "3") (pinfunction "3_3") (pintype "passive"))
    )
    (net (code "15") (name "/DAC_OUT1") (class "Default")
      (node (ref "IC1") (pin "3") (pinfunction "IN+_3") (pintype "input"))
      (node (ref "U1") (pin "20") (pinfunction "PA4_20") (pintype "bidirectional"))
    )
    (net (code "16") (name "/DAC_OUT2") (class "Default")
      (node (ref "IC1") (pin "5") (pinfunction "IN+_5") (pintype "input"))
      (node (ref "U1") (pin "21") (pinfunction "PA5_21") (pintype "bidirectional"))
    )
    (net (code "17") (name "/DC_CAL") (class "Default")
      (node (ref "U1") (pin "40") (pinfunction "PC9_40") (pintype "bidirectional"))
      (node (ref "U5") (pin "12") (pinfunction "DC_CAL_12") (pintype "passive"))
    )
    (net (code "18") (name "/ENC_A") (class "Default")
      (node (ref "JP6") (pin "2") (pinfunction "2_2") (pintype "passive"))
      (node (ref "R18") (pin "1") (pinfunction "1_1") (pintype "passive"))
      (node (ref "U1") (pin "26") (pinfunction "PB0_26") (pintype "bidirectional"))
    )
    (net (code "19") (name "/ENC_B") (class "Default")
      (node (ref "JP6") (pin "3") (pinfunction "3_3") (pintype "passive"))
      (node (ref "R19") (pin "1") (pinfunction "1_1") (pintype "passive"))
      (node (ref "U1") (pin "27") (pinfunction "PB1_27") (pintype "bidirectional"))
    )
    (net (code "20") (name "/ENC_Z") (class "Default")
      (node (ref "JP6") (pin "4") (pinfunction "4_4") (pintype "passive"))
      (node (ref "R20") (pin "1") (pinfunction "1_1") (pintype "passive"))
      (node (ref "U1") (pin "50") (pinfunction "PA15(JTDI)_50") (pintype "bidirectional"))
    )
    (net (code "21") (name "/EN_GATE") (class "Default")
      (node (ref "U1") (pin "33") (pinfunction "PB12_33") (pintype "bidirectional"))
      (node (ref "U5") (pin "16") (pinfunction "EN_GATE_16") (pintype "passive"))
    )
    (net (code "22") (name "/GH_A") (class "Default")
      (node (ref "R43") (pin "1") (pinfunction "1_1") (pintype "passive"))
      (node (ref "U5") (pin "47") (pinfunction "GH_A_47") (pintype "passive"))
    )
    (net (code "23") (name "/GH_B") (class "Default")
      (node (ref "R44") (pin "1") (pinfunction "1_1") (pintype "passive"))
      (node (ref "U5") (pin "42") (pinfunction "GH_B_42") (pintype "passive"))
    )
    (net (code "24") (name "/GH_C") (class "Default")
      (node (ref "R45") (pin "1") (pinfunction "1_1") (pintype "passive"))
      (node (ref "U5") (pin "37") (pinfunction "GH_C_37") (pintype "passive"))
    )
    (net (code "25") (name "/GL_A") (class "Default")
      (node (ref "R50") (pin "1") (pinfunction "1_1") (pintype "passive"))
      (node (ref "U5") (pin "45") (pinfunction "GL_A_45") (pintype "passive"))
    )
    (net (code "26") (name "/GL_B") (class "Default")
      (node (ref "R51") (pin "1") (pinfunction "1_1") (pintype "passive"))
      (node (ref "U5") (pin "40") (pinfunction "GL_B_40") (pintype "passive"))
    )
    (net (code "27") (name "/GL_C") (class "Default")
      (node (ref "R52") (pin "1") (pinfunction "1_1") (pintype "passive"))
      (node (ref "U5") (pin "35") (pinfunction "GL_C_35") (pintype "passive"))
    )
    (net (code "28") (name "/GPIO_1") (class "Default")
      (node (ref "JP11") (pin "1") (pinfunction "1_1") (pintype "passive"))
      (node (ref "R36") (pin "2") (pinfunction "2_2") (pintype "passive"))
      (node (ref "S2") (pin "2") (pinfunction "2_2") (pintype "passive"))
      (node (ref "U1") (pin "14") (pinfunction "PA0-WKUP(PA0)_14") (pintype "bidirectional"))
    )
    (net (code "29") (name "/GPIO_2") (class "Default")
      (node (ref "JP10") (pin "2") (pinfunction "2_2") (pintype "passive"))
      (node (ref "R37") (pin "2") (pinfunction "2_2") (pintype "passive"))
      (node (ref "S3") (pin "2") (pinfunction "2_2") (pintype "passive"))
      (node (ref "U1") (pin "15") (pinfunction "PA1_15") (pintype "bidirectional"))
    )
    (net (code "30") (name "/GPIO_3") (class "Default")
      (node (ref "JP11") (pin "2") (pinfunction "2_2") (pintype "passive"))
      (node (ref "U1") (pin "24") (pinfunction "PC4_24") (pintype "bidirectional"))
    )
    (net (code "31") (name "/GPIO_4") (class "Default")
      (node (ref "JP10") (pin "3") (pinfunction "3_3") (pintype "passive"))
      (node (ref "U1") (pin "38") (pinfunction "PC7_38") (pintype "bidirectional"))
    )
    (net (code "32") (name "/GPIO_5") (class "Default")
      (node (ref "JP11") (pin "3") (pinfunction "3_3") (pintype "passive"))
      (node (ref "U1") (pin "39") (pinfunction "PC8_39") (pintype "bidirectional"))
    )
    (net (code "33") (name "/GPIO_6") (class "Default")
      (node (ref "JP10") (pin "4") (pinfunction "4_4") (pintype "passive"))
      (node (ref "U1") (pin "3") (pinfunction "PC14-OSC32_IN(PC14)_3") (pintype "bidirectional"))
    )
    (net (code "34") (name "/GPIO_7") (class "Default")
      (node (ref "JP11") (pin "4") (pinfunction "4_4") (pintype "passive"))
      (node (ref "U1") (pin "4") (pinfunction "PC15-OSC32_OUT(PC15)_4") (pintype "bidirectional"))
    )
    (net (code "35") (name "/GPIO_8") (class "Default")
      (node (ref "JP10") (pin "5") (pinfunction "5_5") (pintype "passive"))
      (node (ref "U1") (pin "44") (pinfunction "PA11_44") (pintype "bidirectional"))
    )
    (net (code "36") (name "/GPIO_9") (class "Default")
      (node (ref "JP11") (pin "5") (pinfunction "5_5") (pintype "passive"))
      (node (ref "U1") (pin "45") (pinfunction "PA12_45") (pintype "bidirectional"))
    )
    (net (code "37") (name "/I2C_1_SCL") (class "Default")
      (node (ref "JP3") (pin "2") (pinfunction "2_2") (pintype "passive"))
      (node (ref "R3") (pin "1") (pinfunction "1_1") (pintype "passive"))
      (node (ref "U1") (pin "58") (pinfunction "PB6_58") (pintype "bidirectional"))
    )
    (net (code "38") (name "/I2C_1_SDA") (class "Default")
      (node (ref "JP3") (pin "3") (pinfunction "3_3") (pintype "passive"))
      (node (ref "R2") (pin "1") (pinfunction "1_1") (pintype "passive"))
      (node (ref "U1") (pin "59") (pinfunction "PB7_59") (pintype "bidirectional"))
    )
    (net (code "39") (name "/OLED_SCL") (class "Default")
      (node (ref "R6") (pin "2") (pinfunction "2_2") (pintype "passive"))
      (node (ref "U1") (pin "29") (pinfunction "PB10_29") (pintype "bidirectional"))
      (node (ref "U11") (pin "10") (pinfunction "SCL_10") (pintype "passive"))
    )
    (net (code "40") (name "/OLED_SDA") (class "Default")
      (node (ref "R7") (pin "2") (pinfunction "2_2") (pintype "passive"))
      (node (ref "U1") (pin "30") (pinfunction "PB11_30") (pintype "bidirectional"))
      (node (ref "U11") (pin "11") (pinfunction "SDA_11") (pintype "passive"))
    )
    (net (code "41") (name "/RGB_LED") (class "Default")
      (node (ref "U1") (pin "23") (pinfunction "PA7_23") (pintype "bidirectional"))
      (node (ref "U10") (pin "4") (pinfunction "DIN_4") (pintype "passive"))
    )
    (net (code "42") (name "/SCL_A") (class "Default")
      (node (ref "IC2") (pin "6") (pinfunction "SCL_6") (pintype "input"))
      (node (ref "R11") (pin "2") (pinfunction "2_2") (pintype "passive"))
      (node (ref "U1") (pin "61") (pinfunction "PB8_61") (pintype "bidirectional"))
    )
    (net (code "43") (name "/SDA_A") (class "Default")
      (node (ref "IC2") (pin "5") (pinfunction "SDA_5") (pintype "bidirectional"))
      (node (ref "R13") (pin "2") (pinfunction "2_2") (pintype "passive"))
      (node (ref "U1") (pin "62") (pinfunction "PB9_62") (pintype "bidirectional"))
    )
    (net (code "44") (name "/SH_A") (class "Default")
      (node (ref "C52") (pin "2") (pinfunction "2_2") (pintype "passive"))
      (node (ref "JP9") (pin "3") (pinfunction "3_3") (pintype "passive"))
      (node (ref "Q1") (pin "S") (pinfunction "S_S") (pintype "passive"))
      (node (ref "Q2") (pin "S") (pinfunction "S_S") (pintype "passive"))
      (node (ref "Q7") (pin "D") (pinfunction "D_D") (pintype "passive"))
      (node (ref "Q8") (pin "D") (pinfunction "D_D") (pintype "passive"))
      (node (ref "U5") (pin "46") (pinfunction "SH_A_46") (pintype "passive"))
    )
    (net (code "45") (name "/SH_B") (class "Default")
      (node (ref "C53") (pin "2") (pinfunction "2_2") (pintype "passive"))
      (node (ref "JP9") (pin "2") (pinfunction "2_2") (pintype "passive"))
      (node (ref "Q10") (pin "D") (pinfunction "D_D") (pintype "passive"))
      (node (ref "Q3") (pin "S") (pinfunction "S_S") (pintype "passive"))
      (node (ref "Q4") (pin "S") (pinfunction "S_S") (pintype "passive"))
      (node (ref "Q9") (pin "D") (pinfunction "D_D") (pintype "passive"))
      (node (ref "U5") (pin "41") (pinfunction "SH_B_41") (pintype "passive"))
    )
    (net (code "46") (name "/SH_C") (class "Default")
      (node (ref "C55") (pin "2") (pinfunction "2_2") (pintype "passive"))
      (node (ref "JP9") (pin "1") (pinfunction "1_1") (pintype "passive"))
      (node (ref "Q11") (pin "D") (pinfunction "D_D") (pintype "passive"))
      (node (ref "Q12") (pin "D") (pinfunction "D_D") (pintype "passive"))
      (node (ref "Q5") (pin "S") (pinfunction "S_S") (pintype "passive"))
      (node (ref "Q6") (pin "S") (pinfunction "S_S") (pintype "passive"))
      (node (ref "U5") (pin "36") (pinfunction "SH_C_36") (pintype "passive"))
    )
    (net (code "47") (name "/SL_B") (class "Default")
      (node (ref "NT1") (pin "2") (pintype "passive"))
      (node (ref "Q10") (pin "S") (pinfunction "S_S") (pintype "passive"))
      (node (ref "Q9") (pin "S") (pinfunction "S_S") (pintype "passive"))
      (node (ref "R55") (pin "2") (pinfunction "2_2") (pintype "passive"))
      (node (ref "U5") (pin "39") (pinfunction "SL_B_39") (pintype "passive"))
    )
    (net (code "48") (name "/SL_C") (class "Default")
      (node (ref "2") (pin "2") (pinfunction "2_2") (pintype "passive"))
      (node (ref "NT2") (pin "2") (pintype "passive"))
      (node (ref "Q11") (pin "S") (pinfunction "S_S") (pintype "passive"))
      (node (ref "Q12") (pin "S") (pinfunction "S_S") (pintype "passive"))
      (node (ref "U5") (pin "34") (pinfunction "SL_C_34") (pintype "passive"))
    )
    (net (code "49") (name "/SN1") (class "Default")
      (node (ref "NT1") (pin "1") (pintype "passive"))
      (node (ref "R48") (pin "2") (pinfunction "2_2") (pintype "passive"))
    )
    (net (code "50") (name "/SN2") (class "Default")
      (node (ref "NT2") (pin "1") (pintype "passive"))
      (node (ref "R54") (pin "2") (pinfunction "2_2") (pintype "passive"))
    )
    (net (code "51") (name "/SO1") (class "Default")
      (node (ref "C61") (pin "1") (pinfunction "1_1") (pintype "passive"))
      (node (ref "R49") (pin "1") (pinfunction "1_1") (pintype "passive"))
      (node (ref "U1") (pin "8") (pinfunction "PC0_8") (pintype "bidirectional"))
    )
    (net (code "52") (name "/SO2") (class "Default")
      (node (ref "C62") (pin "1") (pinfunction "1_1") (pintype "passive"))
      (node (ref "R53") (pin "1") (pinfunction "1_1") (pintype "passive"))
      (node (ref "U1") (pin "9") (pinfunction "PC1_9") (pintype "bidirectional"))
    )
    (net (code "53") (name "/SP1") (class "Default")
      (node (ref "C57") (pin "2") (pinfunction "2_2") (pintype "passive"))
      (node (ref "NT3") (pin "1") (pintype "passive"))
      (node (ref "U5") (pin "32") (pinfunction "SP1_32") (pintype "passive"))
    )
    (net (code "54") (name "/SP2") (class "Default")
      (node (ref "C63") (pin "2") (pinfunction "2_2") (pintype "passive"))
      (node (ref "NT4") (pin "1") (pintype "passive"))
      (node (ref "U5") (pin "30") (pinfunction "SP2_30") (pintype "passive"))
    )
    (net (code "55") (name "/SPI1_CS") (class "Default")
      (node (ref "JP2") (pin "2") (pinfunction "2_2") (pintype "passive"))
      (node (ref "U1") (pin "28") (pinfunction "PB2-BOOT1(PB2)_28") (pintype "bidirectional"))
    )
    (net (code "56") (name "/SPI1_MISO") (class "Default")
      (node (ref "JP2") (pin "4") (pinfunction "4_4") (pintype "passive"))
      (node (ref "U1") (pin "56") (pinfunction "PB4(NJTRST)_56") (pintype "bidirectional"))
    )
    (net (code "57") (name "/SPI1_MOSI") (class "Default")
      (node (ref "JP2") (pin "5") (pinfunction "5_5") (pintype "passive"))
      (node (ref "U1") (pin "57") (pinfunction "PB5_57") (pintype "bidirectional"))
    )
    (net (code "58") (name "/SPI1_SCK") (class "Default")
      (node (ref "JP2") (pin "3") (pinfunction "3_3") (pintype "passive"))
      (node (ref "U1") (pin "55") (pinfunction "PB3(JTDO/TRACESWO)_55") (pintype "bidirectional"))
    )
    (net (code "59") (name "/SPI_MISO") (class "Default")
      (node (ref "U1") (pin "52") (pinfunction "PC11_52") (pintype "bidirectional"))
      (node (ref "U5") (pin "10") (pinfunction "SDO_10") (pintype "passive"))
    )
    (net (code "60") (name "/SPI_MOSI") (class "Default")
      (node (ref "U1") (pin "53") (pinfunction "PC12_53") (pintype "bidirectional"))
      (node (ref "U5") (pin "9") (pinfunction "SDI_9") (pintype "passive"))
    )
    (net (code "61") (name "/SPI_SCK") (class "Default")
      (node (ref "U1") (pin "51") (pinfunction "PC10_51") (pintype "bidirectional"))
      (node (ref "U5") (pin "11") (pinfunction "SCLK_11") (pintype "passive"))
    )
    (net (code "62") (name "/SWCLK") (class "Default")
      (node (ref "R10") (pin "1") (pinfunction "1_1") (pintype "passive"))
      (node (ref "U1") (pin "49") (pinfunction "PA14(JTCK-SWCLK)_49") (pintype "bidirectional"))
    )
    (net (code "63") (name "/SWDIO") (class "Default")
      (node (ref "R12") (pin "1") (pinfunction "1_1") (pintype "passive"))
      (node (ref "U1") (pin "46") (pinfunction "PA13(JTMS-SWDIO)_46") (pintype "bidirectional"))
    )
    (net (code "64") (name "/TEMP") (class "Default")
      (node (ref "C39") (pin "1") (pinfunction "1_1") (pintype "passive"))
      (node (ref "R26") (pin "2") (pinfunction "2_2") (pintype "passive"))
      (node (ref "U1") (pin "25") (pinfunction "PC5_25") (pintype "bidirectional"))
    )
    (net (code "65") (name "/USART_2_RX") (class "Default")
      (node (ref "U1") (pin "17") (pinfunction "PA3_17") (pintype "bidirectional"))
      (node (ref "U2") (pin "3") (pinfunction "TXD_3") (pintype "passive"))
    )
    (net (code "66") (name "/USART_2_TX") (class "Default")
      (node (ref "U1") (pin "16") (pinfunction "PA2_16") (pintype "bidirectional"))
      (node (ref "U2") (pin "4") (pinfunction "RXD_4") (pintype "passive"))
    )
    (net (code "67") (name "/VBUS_S") (class "Default")
      (node (ref "C22") (pin "1") (pinfunction "1_1") (pintype "passive"))
      (node (ref "R21") (pin "2") (pinfunction "2_2") (pintype "passive"))
      (node (ref "U1") (pin "22") (pinfunction "PA6_22") (pintype "bidirectional"))
    )
    (net (code "68") (name "/nCS") (class "Default")
      (node (ref "U1") (pin "2") (pinfunction "PC13_2") (pintype "bidirectional"))
      (node (ref "U5") (pin "8") (pinfunction "nSCS_8") (pintype "passive"))
    )
    (net (code "69") (name "/nFAULT") (class "Default")
      (node (ref "U1") (pin "54") (pinfunction "PD2_54") (pintype "bidirectional"))
      (node (ref "U5") (pin "6") (pinfunction "nFAULT_6") (pintype "passive"))
    )
    (net (code "70") (name "/nOCTW") (class "Default")
      (node (ref "U1") (pin "37") (pinfunction "PC6_37") (pintype "bidirectional"))
      (node (ref "U5") (pin "5") (pinfunction "nOCTW_5") (pintype "passive"))
    )
    (net (code "71") (name "/nRST") (class "Default")
      (node (ref "C41") (pin "2") (pinfunction "2_2") (pintype "passive"))
      (node (ref "JP5") (pin "5") (pinfunction "5_5") (pintype "passive"))
      (node (ref "R33") (pin "2") (pinfunction "2_2") (pintype "passive"))
      (node (ref "S1") (pin "1") (pinfunction "1_1") (pintype "passive"))
      (node (ref "U1") (pin "7") (pinfunction "NRST_7") (pintype "bidirectional"))
    )
    (net (code "72") (name "AGND") (class "Default")
      (node (ref "C22") (pin "2") (pinfunction "2_2") (pintype "passive"))
      (node (ref "C23") (pin "1") (pinfunction "1_1") (pintype "passive"))
      (node (ref "C24") (pin "2") (pinfunction "2_2") (pintype "passive"))
      (node (ref "C25") (pin "2") (pinfunction "2_2") (pintype "passive"))
      (node (ref "C26") (pin "1") (pinfunction "1_1") (pintype "passive"))
      (node (ref "C35") (pin "1") (pinfunction "1_1") (pintype "passive"))
      (node (ref "C36") (pin "2") (pinfunction "2_2") (pintype "passive"))
      (node (ref "C39") (pin "2") (pinfunction "2_2") (pintype "passive"))
      (node (ref "C4") (pin "1") (pinfunction "1_1") (pintype "passive"))
      (node (ref "C40") (pin "2") (pinfunction "2_2") (pintype "passive"))
      (node (ref "C42") (pin "2") (pinfunction "2_2") (pintype "passive"))
      (node (ref "C56") (pin "1") (pinfunction "1_1") (pintype "passive"))
      (node (ref "C58") (pin "1") (pinfunction "1_1") (pintype "passive"))
      (node (ref "C61") (pin "2") (pinfunction "2_2") (pintype "passive"))
      (node (ref "C62") (pin "2") (pinfunction "2_2") (pintype "passive"))
      (node (ref "IC1") (pin "4") (pinfunction "V-_4") (pintype "power_in"))
      (node (ref "IC3") (pin "4") (pinfunction "V-_4") (pintype "power_in"))
      (node (ref "IC4") (pin "4") (pinfunction "V-_4") (pintype "power_in"))
      (node (ref "JP1") (pin "2") (pinfunction "2_2") (pintype "passive"))
      (node (ref "JP1") (pin "4") (pinfunction "4_4") (pintype "passive"))
      (node (ref "JP4") (pin "2") (pinfunction "2_2") (pintype "passive"))
      (node (ref "JP4") (pin "4") (pinfunction "4_4") (pintype "passive"))
      (node (ref "R23") (pin "1") (pinfunction "1_1") (pintype "passive"))
      (node (ref "R28") (pin "1") (pinfunction "1_1") (pintype "passive"))
      (node (ref "R32") (pin "2") (pinfunction "2_2") (pintype "passive"))
      (node (ref "U1") (pin "12") (pinfunction "VSSA_12") (pintype "power_in"))
      (node (ref "U4") (pin "2") (pinfunction "GND_2") (pintype "passive"))
      (node (ref "U5") (pin "28") (pinfunction "AGND_28") (pintype "passive"))
    )
    (net (code "73") (name "AVCC3v3") (class "Default")
      (node (ref "C23") (pin "2") (pinfunction "2_2") (pintype "passive"))
      (node (ref "C26") (pin "2") (pinfunction "2_2") (pintype "passive"))
      (node (ref "C35") (pin "2") (pinfunction "2_2") (pintype "passive"))
      (node (ref "C36") (pin "1") (pinfunction "1_1") (pintype "passive"))
      (node (ref "C4") (pin "2") (pinfunction "2_2") (pintype "passive"))
      (node (ref "IC1") (pin "8") (pinfunction "V+_8") (pintype "power_in"))
      (node (ref "IC3") (pin "8") (pinfunction "V+_8") (pintype "power_in"))
      (node (ref "IC4") (pin "8") (pinfunction "V+_8") (pintype "power_in"))
      (node (ref "R24") (pin "2") (pinfunction "2_2") (pintype "passive"))
      (node (ref "U1") (pin "13") (pinfunction "VDDA_13") (pintype "power_in"))
      (node (ref "U4") (pin "4") (pinfunction "N/C_4") (pintype "passive"))
      (node (ref "U4") (pin "5") (pinfunction "Vout_5") (pintype "passive"))
      (node (ref "U5") (pin "24") (pinfunction "REF_24") (pintype "passive"))
    )
    (net (code "74") (name "DCBUS") (class "Default")
      (node (ref "C48") (pin "1") (pinfunction "1_1") (pintype "passive"))
      (node (ref "C49") (pin "1") (pinfunction "1_1") (pintype "passive"))
      (node (ref "C50") (pin "1") (pinfunction "1_1") (pintype "passive"))
      (node (ref "C59") (pin "2") (pinfunction "2_2") (pintype "passive"))
      (node (ref "C60") (pin "2") (pinfunction "2_2") (pintype "passive"))
      (node (ref "C64") (pin "2") (pinfunction "2_2") (pintype "passive"))
      (node (ref "C65") (pin "2") (pinfunction "2_2") (pintype "passive"))
      (node (ref "C66") (pin "2") (pinfunction "2_2") (pintype "passive"))
      (node (ref "C67") (pin "2") (pinfunction "2_2") (pintype "passive"))
      (node (ref "C68") (pin "2") (pinfunction "2_2") (pintype "passive"))
      (node (ref "C69") (pin "2") (pinfunction "2_2") (pintype "passive"))
      (node (ref "C70") (pin "2") (pinfunction "2_2") (pintype "passive"))
      (node (ref "C71") (pin "2") (pinfunction "2_2") (pintype "passive"))
      (node (ref "C72") (pin "2") (pinfunction "2_2") (pintype "passive"))
      (node (ref "C73") (pin "2") (pinfunction "2_2") (pintype "passive"))
      (node (ref "C74") (pin "2") (pinfunction "2_2") (pintype "passive"))
      (node (ref "C75") (pin "2") (pinfunction "2_2") (pintype "passive"))
      (node (ref "C76") (pin "2") (pinfunction "2_2") (pintype "passive"))
      (node (ref "JP12") (pin "2") (pinfunction "2_2") (pintype "passive"))
      (node (ref "Q1") (pin "D") (pinfunction "D_D") (pintype "passive"))
      (node (ref "Q2") (pin "D") (pinfunction "D_D") (pintype "passive"))
      (node (ref "Q3") (pin "D") (pinfunction "D_D") (pintype "passive"))
      (node (ref "Q4") (pin "D") (pinfunction "D_D") (pintype "passive"))
      (node (ref "Q5") (pin "D") (pinfunction "D_D") (pintype "passive"))
      (node (ref "Q6") (pin "D") (pinfunction "D_D") (pintype "passive"))
      (node (ref "R15") (pin "2") (pinfunction "2_2") (pintype "passive"))
      (node (ref "U5") (pin "29") (pinfunction "PVDD1_29") (pintype "passive"))
      (node (ref "U5") (pin "53") (pinfunction "PVDD2_53") (pintype "passive"))
      (node (ref "U5") (pin "54") (pinfunction "PVDD2_54") (pintype "passive"))
    )
    (net (code "75") (name "DGND") (class "Default")
      (node (ref "C1") (pin "2") (pinfunction "2_2") (pintype "passive"))
      (node (ref "C10") (pin "1") (pinfunction "1_1") (pintype "passive"))
      (node (ref "C11") (pin "2") (pinfunction "2_2") (pintype "passive"))
      (node (ref "C12") (pin "2") (pinfunction "2_2") (pintype "passive"))
      (node (ref "C13") (pin "2") (pinfunction "2_2") (pintype "passive"))
      (node (ref "C14") (pin "1") (pinfunction "1_1") (pintype "passive"))
      (node (ref "C15") (pin "2") (pinfunction "2_2") (pintype "passive"))
      (node (ref "C16") (pin "2") (pinfunction "2_2") (pintype "passive"))
      (node (ref "C17") (pin "1") (pinfunction "1_1") (pintype "passive"))
      (node (ref "C18") (pin "1") (pinfunction "1_1") (pintype "passive"))
      (node (ref "C20") (pin "2") (pinfunction "2_2") (pintype "passive"))
      (node (ref "C21") (pin "2") (pinfunction "2_2") (pintype "passive"))
      (node (ref "C27") (pin "1") (pinfunction "1_1") (pintype "passive"))
      (node (ref "C28") (pin "1") (pinfunction "1_1") (pintype "passive"))
      (node (ref "C29") (pin "1") (pinfunction "1_1") (pintype "passive"))
      (node (ref "C3") (pin "2") (pinfunction "2_2") (pintype "passive"))
      (node (ref "C30") (pin "1") (pinfunction "1_1") (pintype "passive"))
      (node (ref "C41") (pin "1") (pinfunction "1_1") (pintype "passive"))
      (node (ref "C45") (pin "2") (pinfunction "2_2") (pintype "passive"))
      (node (ref "C6") (pin "2") (pinfunction "2_2") (pintype "passive"))
      (node (ref "C7") (pin "1") (pinfunction "1_1") (pintype "passive"))
      (node (ref "C8") (pin "1") (pinfunction "1_1") (pintype "passive"))
      (node (ref "C9") (pin "2") (pinfunction "2_2") (pintype "passive"))
      (node (ref "IC2") (pin "1") (pinfunction "A0_1") (pintype "input"))
      (node (ref "IC2") (pin "2") (pinfunction "A1_2") (pintype "input"))
      (node (ref "IC2") (pin "3") (pinfunction "A2_3") (pintype "input"))
      (node (ref "IC2") (pin "4") (pinfunction "GND_4") (pintype "passive"))
      (node (ref "IC2") (pin "7") (pinfunction "WP_7") (pintype "passive"))
      (node (ref "JP10") (pin "1") (pinfunction "1_1") (pintype "passive"))
      (node (ref "JP2") (pin "6") (pinfunction "6_6") (pintype "passive"))
      (node (ref "JP3") (pin "4") (pinfunction "4_4") (pintype "passive"))
      (node (ref "JP5") (pin "3") (pinfunction "3_3") (pintype "passive"))
      (node (ref "JP6") (pin "5") (pinfunction "5_5") (pintype "passive"))
      (node (ref "R14") (pin "1") (pinfunction "1_1") (pintype "passive"))
      (node (ref "R17") (pin "2") (pinfunction "2_2") (pintype "passive"))
      (node (ref "R31") (pin "2") (pinfunction "2_2") (pintype "passive"))
      (node (ref "R40") (pin "1") (pinfunction "1_1") (pintype "passive"))
      (node (ref "R42") (pin "2") (pinfunction "2_2") (pintype "passive"))
      (node (ref "R46") (pin "1") (pinfunction "1_1") (pintype "passive"))
      (node (ref "R47") (pin "2") (pinfunction "2_2") (pintype "passive"))
      (node (ref "R9") (pin "1") (pinfunction "1_1") (pintype "passive"))
      (node (ref "S1") (pin "2") (pinfunction "2_2") (pintype "passive"))
      (node (ref "S2") (pin "1") (pinfunction "1_1") (pintype "passive"))
      (node (ref "S3") (pin "1") (pinfunction "1_1") (pintype "passive"))
      (node (ref "U1") (pin "18") (pinfunction "VSS_18") (pintype "power_in"))
      (node (ref "U1") (pin "63") (pinfunction "VSS_63") (pintype "power_in"))
      (node (ref "U10") (pin "3") (pinfunction "GND_3") (pintype "passive"))
      (node (ref "U11") (pin "7") (pinfunction "VSS_7") (pintype "passive"))
      (node (ref "U2") (pin "8") (pinfunction "GND_8") (pintype "passive"))
      (node (ref "U3") (pin "1") (pinfunction "GND_1") (pintype "passive"))
      (node (ref "USB1") (pin "5") (pinfunction "GND_5") (pintype "passive"))
      (node (ref "XT1") (pin "G") (pintype "passive"))
      (node (ref "XT2") (pin "G") (pintype "passive"))
    )
    (net (code "76") (name "GND") (class "Default")
      (node (ref "C31") (pin "2") (pinfunction "2_2") (pintype "passive"))
      (node (ref "C32") (pin "2") (pinfunction "2_2") (pintype "passive"))
      (node (ref "C46") (pin "2") (pinfunction "2_2") (pintype "passive"))
      (node (ref "C47") (pin "2") (pinfunction "2_2") (pintype "passive"))
      (node (ref "C48") (pin "2") (pinfunction "2_2") (pintype "passive"))
      (node (ref "C49") (pin "2") (pinfunction "2_2") (pintype "passive"))
      (node (ref "C60") (pin "1") (pinfunction "1_1") (pintype "passive"))
      (node (ref "D6") (pin "1") (pinfunction "A_1") (pintype "passive"))
      (node (ref "E1") (pin "2") (pinfunction "K_2") (pintype "passive"))
      (node (ref "R30") (pin "2") (pinfunction "2_2") (pintype "passive"))
      (node (ref "R31") (pin "1") (pinfunction "1_1") (pintype "passive"))
      (node (ref "R32") (pin "1") (pinfunction "1_1") (pintype "passive"))
      (node (ref "U5") (pin "57") (pinfunction "GND_(PowerPAD)_57") (pintype "passive"))
    )
    (net (code "77") (name "GVDD") (class "Default")
      (node (ref "R47") (pin "1") (pinfunction "1_1") (pintype "passive"))
      (node (ref "U5") (pin "13") (pinfunction "GVDD_13") (pintype "passive"))
    )
    (net (code "78") (name "Net-(C47-Pad1)") (class "Default")
      (node (ref "C47") (pin "1") (pinfunction "1_1") (pintype "passive"))
      (node (ref "R35") (pin "2") (pinfunction "2_2") (pintype "passive"))
    )
    (net (code "79") (name "Net-(D1-A)") (class "Default")
      (node (ref "C16") (pin "1") (pinfunction "1_1") (pintype "passive"))
      (node (ref "D1") (pin "1") (pinfunction "A_1") (pintype "passive"))
      (node (ref "R8") (pin "2") (pinfunction "2_2") (pintype "passive"))
      (node (ref "U11") (pin "9") (pinfunction "~{RES}_9") (pintype "passive"))
    )
    (net (code "80") (name "Net-(D6-K)") (class "Default")
      (node (ref "C51") (pin "2") (pinfunction "2_2") (pintype "passive"))
      (node (ref "D6") (pin "2") (pinfunction "K_2") (pintype "passive"))
      (node (ref "L1") (pin "1") (pinfunction "1_1") (pintype "passive"))
      (node (ref "U5") (pin "50") (pinfunction "PH_50") (pintype "passive"))
      (node (ref "U5") (pin "51") (pinfunction "PH_51") (pintype "passive"))
    )
    (net (code "81") (name "Net-(IC3A-IN+)") (class "Default")
      (node (ref "C24") (pin "1") (pinfunction "1_1") (pintype "passive"))
      (node (ref "IC3") (pin "3") (pinfunction "IN+_3") (pintype "input"))
      (node (ref "R15") (pin "1") (pinfunction "1_1") (pintype "passive"))
      (node (ref "R23") (pin "2") (pinfunction "2_2") (pintype "passive"))
    )
    (net (code "82") (name "Net-(IC3A-IN-)") (class "Default")
      (node (ref "IC3") (pin "1") (pinfunction "OUT_1") (pintype "output"))
      (node (ref "IC3") (pin "2") (pinfunction "IN-_2") (pintype "input"))
      (node (ref "R21") (pin "1") (pinfunction "1_1") (pintype "passive"))
    )
    (net (code "83") (name "Net-(IC3B-IN+)") (class "Default")
      (node (ref "C40") (pin "1") (pinfunction "1_1") (pintype "passive"))
      (node (ref "IC3") (pin "5") (pinfunction "IN+_5") (pintype "input"))
      (node (ref "R24") (pin "1") (pinfunction "1_1") (pintype "passive"))
      (node (ref "R28") (pin "2") (pinfunction "2_2") (pintype "passive"))
    )
    (net (code "84") (name "Net-(IC3B-IN-)") (class "Default")
      (node (ref "IC3") (pin "6") (pinfunction "IN-_6") (pintype "input"))
      (node (ref "IC3") (pin "7") (pinfunction "OUT_7") (pintype "output"))
      (node (ref "R26") (pin "1") (pinfunction "1_1") (pintype "passive"))
    )
    (net (code "85") (name "Net-(IC4A-IN-)") (class "Default")
      (node (ref "IC4") (pin "1") (pinfunction "OUT_1") (pintype "output"))
      (node (ref "IC4") (pin "2") (pinfunction "IN-_2") (pintype "input"))
      (node (ref "R22") (pin "1") (pinfunction "1_1") (pintype "passive"))
    )
    (net (code "86") (name "Net-(IC4B-IN-)") (class "Default")
      (node (ref "IC4") (pin "6") (pinfunction "IN-_6") (pintype "input"))
      (node (ref "IC4") (pin "7") (pinfunction "OUT_7") (pintype "output"))
      (node (ref "R27") (pin "1") (pinfunction "1_1") (pintype "passive"))
    )
    (net (code "87") (name "Net-(JP5-Pad2)") (class "Default")
      (node (ref "JP5") (pin "2") (pinfunction "2_2") (pintype "passive"))
      (node (ref "R10") (pin "2") (pinfunction "2_2") (pintype "passive"))
    )
    (net (code "88") (name "Net-(JP5-Pad4)") (class "Default")
      (node (ref "JP5") (pin "4") (pinfunction "4_4") (pintype "passive"))
      (node (ref "R12") (pin "2") (pinfunction "2_2") (pintype "passive"))
    )
    (net (code "89") (name "Net-(LED1-PadK)") (class "Default")
      (node (ref "LED1") (pin "K") (pinfunction "K_K") (pintype "passive"))
      (node (ref "R17") (pin "1") (pinfunction "1_1") (pintype "passive"))
    )
    (net (code "90") (name "Net-(Q1-PadG)") (class "Default")
      (node (ref "Q1") (pin "G") (pinfunction "G_G") (pintype "passive"))
      (node (ref "Q2") (pin "G") (pinfunction "G_G") (pintype "passive"))
      (node (ref "R43") (pin "2") (pinfunction "2_2") (pintype "passive"))
    )
    (net (code "91") (name "Net-(Q3-PadG)") (class "Default")
      (node (ref "Q3") (pin "G") (pinfunction "G_G") (pintype "passive"))
      (node (ref "Q4") (pin "G") (pinfunction "G_G") (pintype "passive"))
      (node (ref "R44") (pin "2") (pinfunction "2_2") (pintype "passive"))
    )
    (net (code "92") (name "Net-(Q5-PadG)") (class "Default")
      (node (ref "Q5") (pin "G") (pinfunction "G_G") (pintype "passive"))
      (node (ref "Q6") (pin "G") (pinfunction "G_G") (pintype "passive"))
      (node (ref "R45") (pin "2") (pinfunction "2_2") (pintype "passive"))
    )
    (net (code "93") (name "Net-(Q7-PadG)") (class "Default")
      (node (ref "Q7") (pin "G") (pinfunction "G_G") (pintype "passive"))
      (node (ref "Q8") (pin "G") (pinfunction "G_G") (pintype "passive"))
      (node (ref "R50") (pin "2") (pinfunction "2_2") (pintype "passive"))
    )
    (net (code "94") (name "Net-(Q10-PadG)") (class "Default")
      (node (ref "Q10") (pin "G") (pinfunction "G_G") (pintype "passive"))
      (node (ref "Q9") (pin "G") (pinfunction "G_G") (pintype "passive"))
      (node (ref "R51") (pin "2") (pinfunction "2_2") (pintype "passive"))
    )
    (net (code "95") (name "Net-(Q11-PadG)") (class "Default")
      (node (ref "Q11") (pin "G") (pinfunction "G_G") (pintype "passive"))
      (node (ref "Q12") (pin "G") (pinfunction "G_G") (pintype "passive"))
      (node (ref "R52") (pin "2") (pinfunction "2_2") (pintype "passive"))
    )
    (net (code "96") (name "Net-(U1A-PH0-OSC_IN(PH0))") (class "Default")
      (node (ref "C10") (pin "2") (pinfunction "2_2") (pintype "passive"))
      (node (ref "U1") (pin "5") (pinfunction "PH0-OSC_IN(PH0)_5") (pintype "bidirectional"))
      (node (ref "XT2") (pin "3") (pintype "passive"))
    )
    (net (code "97") (name "Net-(U1A-PH1-OSC_OUT(PH1))") (class "Default")
      (node (ref "C14") (pin "2") (pinfunction "2_2") (pintype "passive"))
      (node (ref "U1") (pin "6") (pinfunction "PH1-OSC_OUT(PH1)_6") (pintype "bidirectional"))
      (node (ref "XT2") (pin "1") (pintype "passive"))
    )
    (net (code "98") (name "Net-(U1A-VCAP_1)") (class "Default")
      (node (ref "C18") (pin "2") (pinfunction "2_2") (pintype "passive"))
      (node (ref "U1") (pin "31") (pinfunction "VCAP_1_31") (pintype "power_in"))
    )
    (net (code "99") (name "Net-(U1A-VCAP_2)") (class "Default")
      (node (ref "C17") (pin "2") (pinfunction "2_2") (pintype "passive"))
      (node (ref "U1") (pin "47") (pinfunction "VCAP_2_47") (pintype "power_in"))
    )
    (net (code "100") (name "Net-(U2-VD+)") (class "Default")
      (node (ref "R5") (pin "2") (pinfunction "2_2") (pintype "passive"))
      (node (ref "U2") (pin "6") (pinfunction "VD+_6") (pintype "passive"))
    )
    (net (code "101") (name "Net-(U2-VD-)") (class "Default")
      (node (ref "R4") (pin "2") (pinfunction "2_2") (pintype "passive"))
      (node (ref "U2") (pin "7") (pinfunction "VD-_7") (pintype "passive"))
    )
    (net (code "102") (name "Net-(U2-X0)") (class "Default")
      (node (ref "C9") (pin "1") (pinfunction "1_1") (pintype "passive"))
      (node (ref "U2") (pin "10") (pinfunction "X0_10") (pintype "passive"))
      (node (ref "XT1") (pin "1") (pintype "passive"))
    )
    (net (code "103") (name "Net-(U2-X1)") (class "Default")
      (node (ref "C6") (pin "1") (pinfunction "1_1") (pintype "passive"))
      (node (ref "U2") (pin "9") (pinfunction "X1_9") (pintype "passive"))
      (node (ref "XT1") (pin "3") (pintype "passive"))
    )
    (net (code "104") (name "Net-(U5-AVDD)") (class "Default")
      (node (ref "C58") (pin "2") (pinfunction "2_2") (pintype "passive"))
      (node (ref "U5") (pin "27") (pinfunction "AVDD_27") (pintype "passive"))
    )
    (net (code "105") (name "Net-(U5-BST_A)") (class "Default")
      (node (ref "C52") (pin "1") (pinfunction "1_1") (pintype "passive"))
      (node (ref "U5") (pin "48") (pinfunction "BST_A_48") (pintype "passive"))
    )
    (net (code "106") (name "Net-(U5-BST_B)") (class "Default")
      (node (ref "C53") (pin "1") (pinfunction "1_1") (pintype "passive"))
      (node (ref "U5") (pin "43") (pinfunction "BST_B_43") (pintype "passive"))
    )
    (net (code "107") (name "Net-(U5-BST_BK)") (class "Default")
      (node (ref "C51") (pin "1") (pinfunction "1_1") (pintype "passive"))
      (node (ref "U5") (pin "52") (pinfunction "BST_BK_52") (pintype "passive"))
    )
    (net (code "108") (name "Net-(U5-BST_C)") (class "Default")
      (node (ref "C55") (pin "1") (pinfunction "1_1") (pintype "passive"))
      (node (ref "U5") (pin "38") (pinfunction "BST_C_38") (pintype "passive"))
    )
    (net (code "109") (name "Net-(U5-COMP)") (class "Default")
      (node (ref "C46") (pin "1") (pinfunction "1_1") (pintype "passive"))
      (node (ref "R35") (pin "1") (pinfunction "1_1") (pintype "passive"))
      (node (ref "U5") (pin "2") (pinfunction "COMP_2") (pintype "passive"))
    )
    (net (code "110") (name "Net-(U5-CP1)") (class "Default")
      (node (ref "C54") (pin "1") (pinfunction "1_1") (pintype "passive"))
      (node (ref "U5") (pin "14") (pinfunction "CP1_14") (pintype "passive"))
    )
    (net (code "111") (name "Net-(U5-CP2)") (class "Default")
      (node (ref "C54") (pin "2") (pinfunction "2_2") (pintype "passive"))
      (node (ref "U5") (pin "15") (pinfunction "CP2_15") (pintype "passive"))
    )
    (net (code "112") (name "Net-(U5-DTC)") (class "Default")
      (node (ref "R46") (pin "2") (pinfunction "2_2") (pintype "passive"))
      (node (ref "U5") (pin "7") (pinfunction "DTC_7") (pintype "passive"))
    )
    (net (code "113") (name "Net-(U5-DVDD)") (class "Default")
      (node (ref "C56") (pin "2") (pinfunction "2_2") (pintype "passive"))
      (node (ref "U5") (pin "23") (pinfunction "DVDD_23") (pintype "passive"))
    )
    (net (code "114") (name "Net-(U5-RT_CLK)") (class "Default")
      (node (ref "R40") (pin "2") (pinfunction "2_2") (pintype "passive"))
      (node (ref "U5") (pin "1") (pinfunction "RT_CLK_1") (pintype "passive"))
    )
    (net (code "115") (name "Net-(U5-SN1)") (class "Default")
      (node (ref "C57") (pin "1") (pinfunction "1_1") (pintype "passive"))
      (node (ref "R48") (pin "1") (pinfunction "1_1") (pintype "passive"))
      (node (ref "U5") (pin "33") (pinfunction "SN1_33") (pintype "passive"))
    )
    (net (code "116") (name "Net-(U5-SN2)") (class "Default")
      (node (ref "C63") (pin "1") (pinfunction "1_1") (pintype "passive"))
      (node (ref "R54") (pin "1") (pinfunction "1_1") (pintype "passive"))
      (node (ref "U5") (pin "31") (pinfunction "SN2_31") (pintype "passive"))
    )
    (net (code "117") (name "Net-(U5-SO1)") (class "Default")
      (node (ref "R49") (pin "2") (pinfunction "2_2") (pintype "passive"))
      (node (ref "U5") (pin "25") (pinfunction "SO1_25") (pintype "passive"))
    )
    (net (code "118") (name "Net-(U5-SO2)") (class "Default")
      (node (ref "R53") (pin "2") (pinfunction "2_2") (pintype "passive"))
      (node (ref "U5") (pin "26") (pinfunction "SO2_26") (pintype "passive"))
    )
    (net (code "119") (name "Net-(U5-VSENSE)") (class "Default")
      (node (ref "R41") (pin "2") (pinfunction "2_2") (pintype "passive"))
      (node (ref "R42") (pin "1") (pinfunction "1_1") (pintype "passive"))
      (node (ref "U5") (pin "3") (pinfunction "VSENSE_3") (pintype "passive"))
    )
    (net (code "120") (name "Net-(U11-C1N)") (class "Default")
      (node (ref "C5") (pin "2") (pinfunction "2_2") (pintype "passive"))
      (node (ref "U11") (pin "4") (pinfunction "C1N_4") (pintype "passive"))
    )
    (net (code "121") (name "Net-(U11-C1P)") (class "Default")
      (node (ref "C5") (pin "1") (pinfunction "1_1") (pintype "passive"))
      (node (ref "U11") (pin "3") (pinfunction "C1P_3") (pintype "passive"))
    )
    (net (code "122") (name "Net-(U11-C2N)") (class "Default")
      (node (ref "C2") (pin "1") (pinfunction "1_1") (pintype "passive"))
      (node (ref "U11") (pin "2") (pinfunction "C2N_2") (pintype "passive"))
    )
    (net (code "123") (name "Net-(U11-C2P)") (class "Default")
      (node (ref "C2") (pin "2") (pinfunction "2_2") (pintype "passive"))
      (node (ref "U11") (pin "1") (pinfunction "C2P_1") (pintype "passive"))
    )
    (net (code "124") (name "Net-(U11-IREF)") (class "Default")
      (node (ref "R9") (pin "2") (pinfunction "2_2") (pintype "passive"))
      (node (ref "U11") (pin "12") (pinfunction "IREF_12") (pintype "passive"))
    )
    (net (code "125") (name "Net-(U11-VCC)") (class "Default")
      (node (ref "C11") (pin "1") (pinfunction "1_1") (pintype "passive"))
      (node (ref "C12") (pin "1") (pinfunction "1_1") (pintype "passive"))
      (node (ref "U11") (pin "14") (pinfunction "VCC_14") (pintype "passive"))
    )
    (net (code "126") (name "Net-(U11-VCOMH)") (class "Default")
      (node (ref "C13") (pin "1") (pinfunction "1_1") (pintype "passive"))
      (node (ref "U11") (pin "13") (pinfunction "VCOMH_13") (pintype "passive"))
    )
    (net (code "127") (name "Net-(U11-VDD)") (class "Default")
      (node (ref "C7") (pin "2") (pinfunction "2_2") (pintype "passive"))
      (node (ref "C8") (pin "2") (pinfunction "2_2") (pintype "passive"))
      (node (ref "U11") (pin "8") (pinfunction "VDD_8") (pintype "passive"))
    )
    (net (code "128") (name "Net-(USB1-+5V)") (class "Default")
      (node (ref "R1") (pin "1") (pinfunction "1_1") (pintype "passive"))
      (node (ref "USB1") (pin "1") (pinfunction "+5V_1") (pintype "passive"))
    )
    (net (code "129") (name "Net-(USB1-D+)") (class "Default")
      (node (ref "R5") (pin "1") (pinfunction "1_1") (pintype "passive"))
      (node (ref "USB1") (pin "3") (pinfunction "D+_3") (pintype "passive"))
    )
    (net (code "130") (name "Net-(USB1-D-)") (class "Default")
      (node (ref "R4") (pin "1") (pinfunction "1_1") (pintype "passive"))
      (node (ref "USB1") (pin "2") (pinfunction "D-_2") (pintype "passive"))
    )
    (net (code "131") (name "PGND") (class "Default")
      (node (ref "2") (pin "1") (pinfunction "1_1") (pintype "passive"))
      (node (ref "C50") (pin "2") (pinfunction "2_2") (pintype "passive"))
      (node (ref "C59") (pin "1") (pinfunction "1_1") (pintype "passive"))
      (node (ref "C64") (pin "1") (pinfunction "1_1") (pintype "passive"))
      (node (ref "C65") (pin "1") (pinfunction "1_1") (pintype "passive"))
      (node (ref "C66") (pin "1") (pinfunction "1_1") (pintype "passive"))
      (node (ref "C67") (pin "1") (pinfunction "1_1") (pintype "passive"))
      (node (ref "C68") (pin "1") (pinfunction "1_1") (pintype "passive"))
      (node (ref "C69") (pin "1") (pinfunction "1_1") (pintype "passive"))
      (node (ref "C70") (pin "1") (pinfunction "1_1") (pintype "passive"))
      (node (ref "C71") (pin "1") (pinfunction "1_1") (pintype "passive"))
      (node (ref "C72") (pin "1") (pinfunction "1_1") (pintype "passive"))
      (node (ref "C73") (pin "1") (pinfunction "1_1") (pintype "passive"))
      (node (ref "C74") (pin "1") (pinfunction "1_1") (pintype "passive"))
      (node (ref "C75") (pin "1") (pinfunction "1_1") (pintype "passive"))
      (node (ref "C76") (pin "1") (pinfunction "1_1") (pintype "passive"))
      (node (ref "JP12") (pin "1") (pinfunction "1_1") (pintype "passive"))
      (node (ref "NT3") (pin "2") (pintype "passive"))
      (node (ref "NT4") (pin "2") (pintype "passive"))
      (node (ref "Q7") (pin "S") (pinfunction "S_S") (pintype "passive"))
      (node (ref "Q8") (pin "S") (pinfunction "S_S") (pintype "passive"))
      (node (ref "R30") (pin "1") (pinfunction "1_1") (pintype "passive"))
      (node (ref "R55") (pin "1") (pinfunction "1_1") (pintype "passive"))
      (node (ref "U5") (pin "44") (pinfunction "SL_A_44") (pintype "passive"))
    )
    (net (code "132") (name "VCC3v3") (class "Default")
      (node (ref "C1") (pin "1") (pinfunction "1_1") (pintype "passive"))
      (node (ref "C15") (pin "1") (pinfunction "1_1") (pintype "passive"))
      (node (ref "C20") (pin "1") (pinfunction "1_1") (pintype "passive"))
      (node (ref "C21") (pin "1") (pinfunction "1_1") (pintype "passive"))
      (node (ref "C27") (pin "2") (pinfunction "2_2") (pintype "passive"))
      (node (ref "C28") (pin "2") (pinfunction "2_2") (pintype "passive"))
      (node (ref "C29") (pin "2") (pinfunction "2_2") (pintype "passive"))
      (node (ref "C3") (pin "1") (pinfunction "1_1") (pintype "passive"))
      (node (ref "C30") (pin "2") (pinfunction "2_2") (pintype "passive"))
      (node (ref "D1") (pin "2") (pinfunction "K_2") (pintype "passive"))
      (node (ref "IC2") (pin "8") (pinfunction "VCC_8") (pintype "power_in"))
      (node (ref "JP2") (pin "1") (pinfunction "1_1") (pintype "passive"))
      (node (ref "JP3") (pin "1") (pinfunction "1_1") (pintype "passive"))
      (node (ref "JP5") (pin "1") (pinfunction "1_1") (pintype "passive"))
      (node (ref "JP6") (pin "1") (pinfunction "1_1") (pintype "passive"))
      (node (ref "LED1") (pin "A") (pinfunction "A_A") (pintype "passive"))
      (node (ref "R11") (pin "1") (pinfunction "1_1") (pintype "passive"))
      (node (ref "R13") (pin "1") (pinfunction "1_1") (pintype "passive"))
      (node (ref "R18") (pin "2") (pinfunction "2_2") (pintype "passive"))
      (node (ref "R19") (pin "2") (pinfunction "2_2") (pintype "passive"))
      (node (ref "R2") (pin "2") (pinfunction "2_2") (pintype "passive"))
      (node (ref "R20") (pin "2") (pinfunction "2_2") (pintype "passive"))
      (node (ref "R3") (pin "2") (pinfunction "2_2") (pintype "passive"))
      (node (ref "R33") (pin "1") (pinfunction "1_1") (pintype "passive"))
      (node (ref "R36") (pin "1") (pinfunction "1_1") (pintype "passive"))
      (node (ref "R37") (pin "1") (pinfunction "1_1") (pintype "passive"))
      (node (ref "R6") (pin "1") (pinfunction "1_1") (pintype "passive"))
      (node (ref "R7") (pin "1") (pinfunction "1_1") (pintype "passive"))
      (node (ref "R8") (pin "1") (pinfunction "1_1") (pintype "passive"))
      (node (ref "U1") (pin "1") (pinfunction "VBAT_1") (pintype "power_in"))
      (node (ref "U1") (pin "19") (pinfunction "VDD_19") (pintype "power_in"))
      (node (ref "U1") (pin "32") (pinfunction "VDD_32") (pintype "power_in"))
      (node (ref "U1") (pin "48") (pinfunction "VDD_48") (pintype "power_in"))
      (node (ref "U1") (pin "64") (pinfunction "VDD_64") (pintype "power_in"))
      (node (ref "U11") (pin "5") (pinfunction "VBAT_5") (pintype "passive"))
      (node (ref "U2") (pin "19") (pinfunction "VCC_19") (pintype "passive"))
      (node (ref "U2") (pin "5") (pinfunction "V3_5") (pintype "passive"))
      (node (ref "U3") (pin "2") (pinfunction "Vout_2") (pintype "passive"))
      (node (ref "U3") (pin "4") (pinfunction "Vout_(tab)_4") (pintype "passive"))
      (node (ref "U5") (pin "49") (pinfunction "VDD_SPI_49") (pintype "passive"))
    )
    (net (code "133") (name "unconnected-(U2-ACT#-Pad2)") (class "Default")
      (node (ref "U2") (pin "2") (pinfunction "ACT#_2") (pintype "passive+no_connect"))
    )
    (net (code "134") (name "unconnected-(U2-TNOW-Pad17)") (class "Default")
      (node (ref "U2") (pin "17") (pinfunction "TNOW_17") (pintype "passive+no_connect"))
    )
    (net (code "135") (name "unconnected-(U5-EN_BUCK-Pad55)") (class "Default")
      (node (ref "U5") (pin "55") (pinfunction "EN_BUCK_55") (pintype "passive"))
    )
    (net (code "136") (name "unconnected-(U5-PWRGD-Pad4)") (class "Default")
      (node (ref "U5") (pin "4") (pinfunction "PWRGD_4") (pintype "passive"))
    )
    (net (code "137") (name "unconnected-(U5-SS_TR-Pad56)") (class "Default")
      (node (ref "U5") (pin "56") (pinfunction "SS_TR_56") (pintype "passive"))
    )
    (net (code "138") (name "unconnected-(U10-DOUT-Pad2)") (class "Default")
      (node (ref "U10") (pin "2") (pinfunction "DOUT_2") (pintype "passive"))
    )
    (net (code "139") (name "unconnected-(U11-VBREF-Pad6)") (class "Default")
      (node (ref "U11") (pin "6") (pinfunction "VBREF_6") (pintype "passive+no_connect"))
    )
    (net (code "140") (name "unconnected-(USB1-ID-Pad4)") (class "Default")
      (node (ref "USB1") (pin "4") (pinfunction "ID_4") (pintype "passive+no_connect"))
    )
  )
)
